# WukongY003.net
KiCad netlist of a schematic drawn in EasyEDA Pro
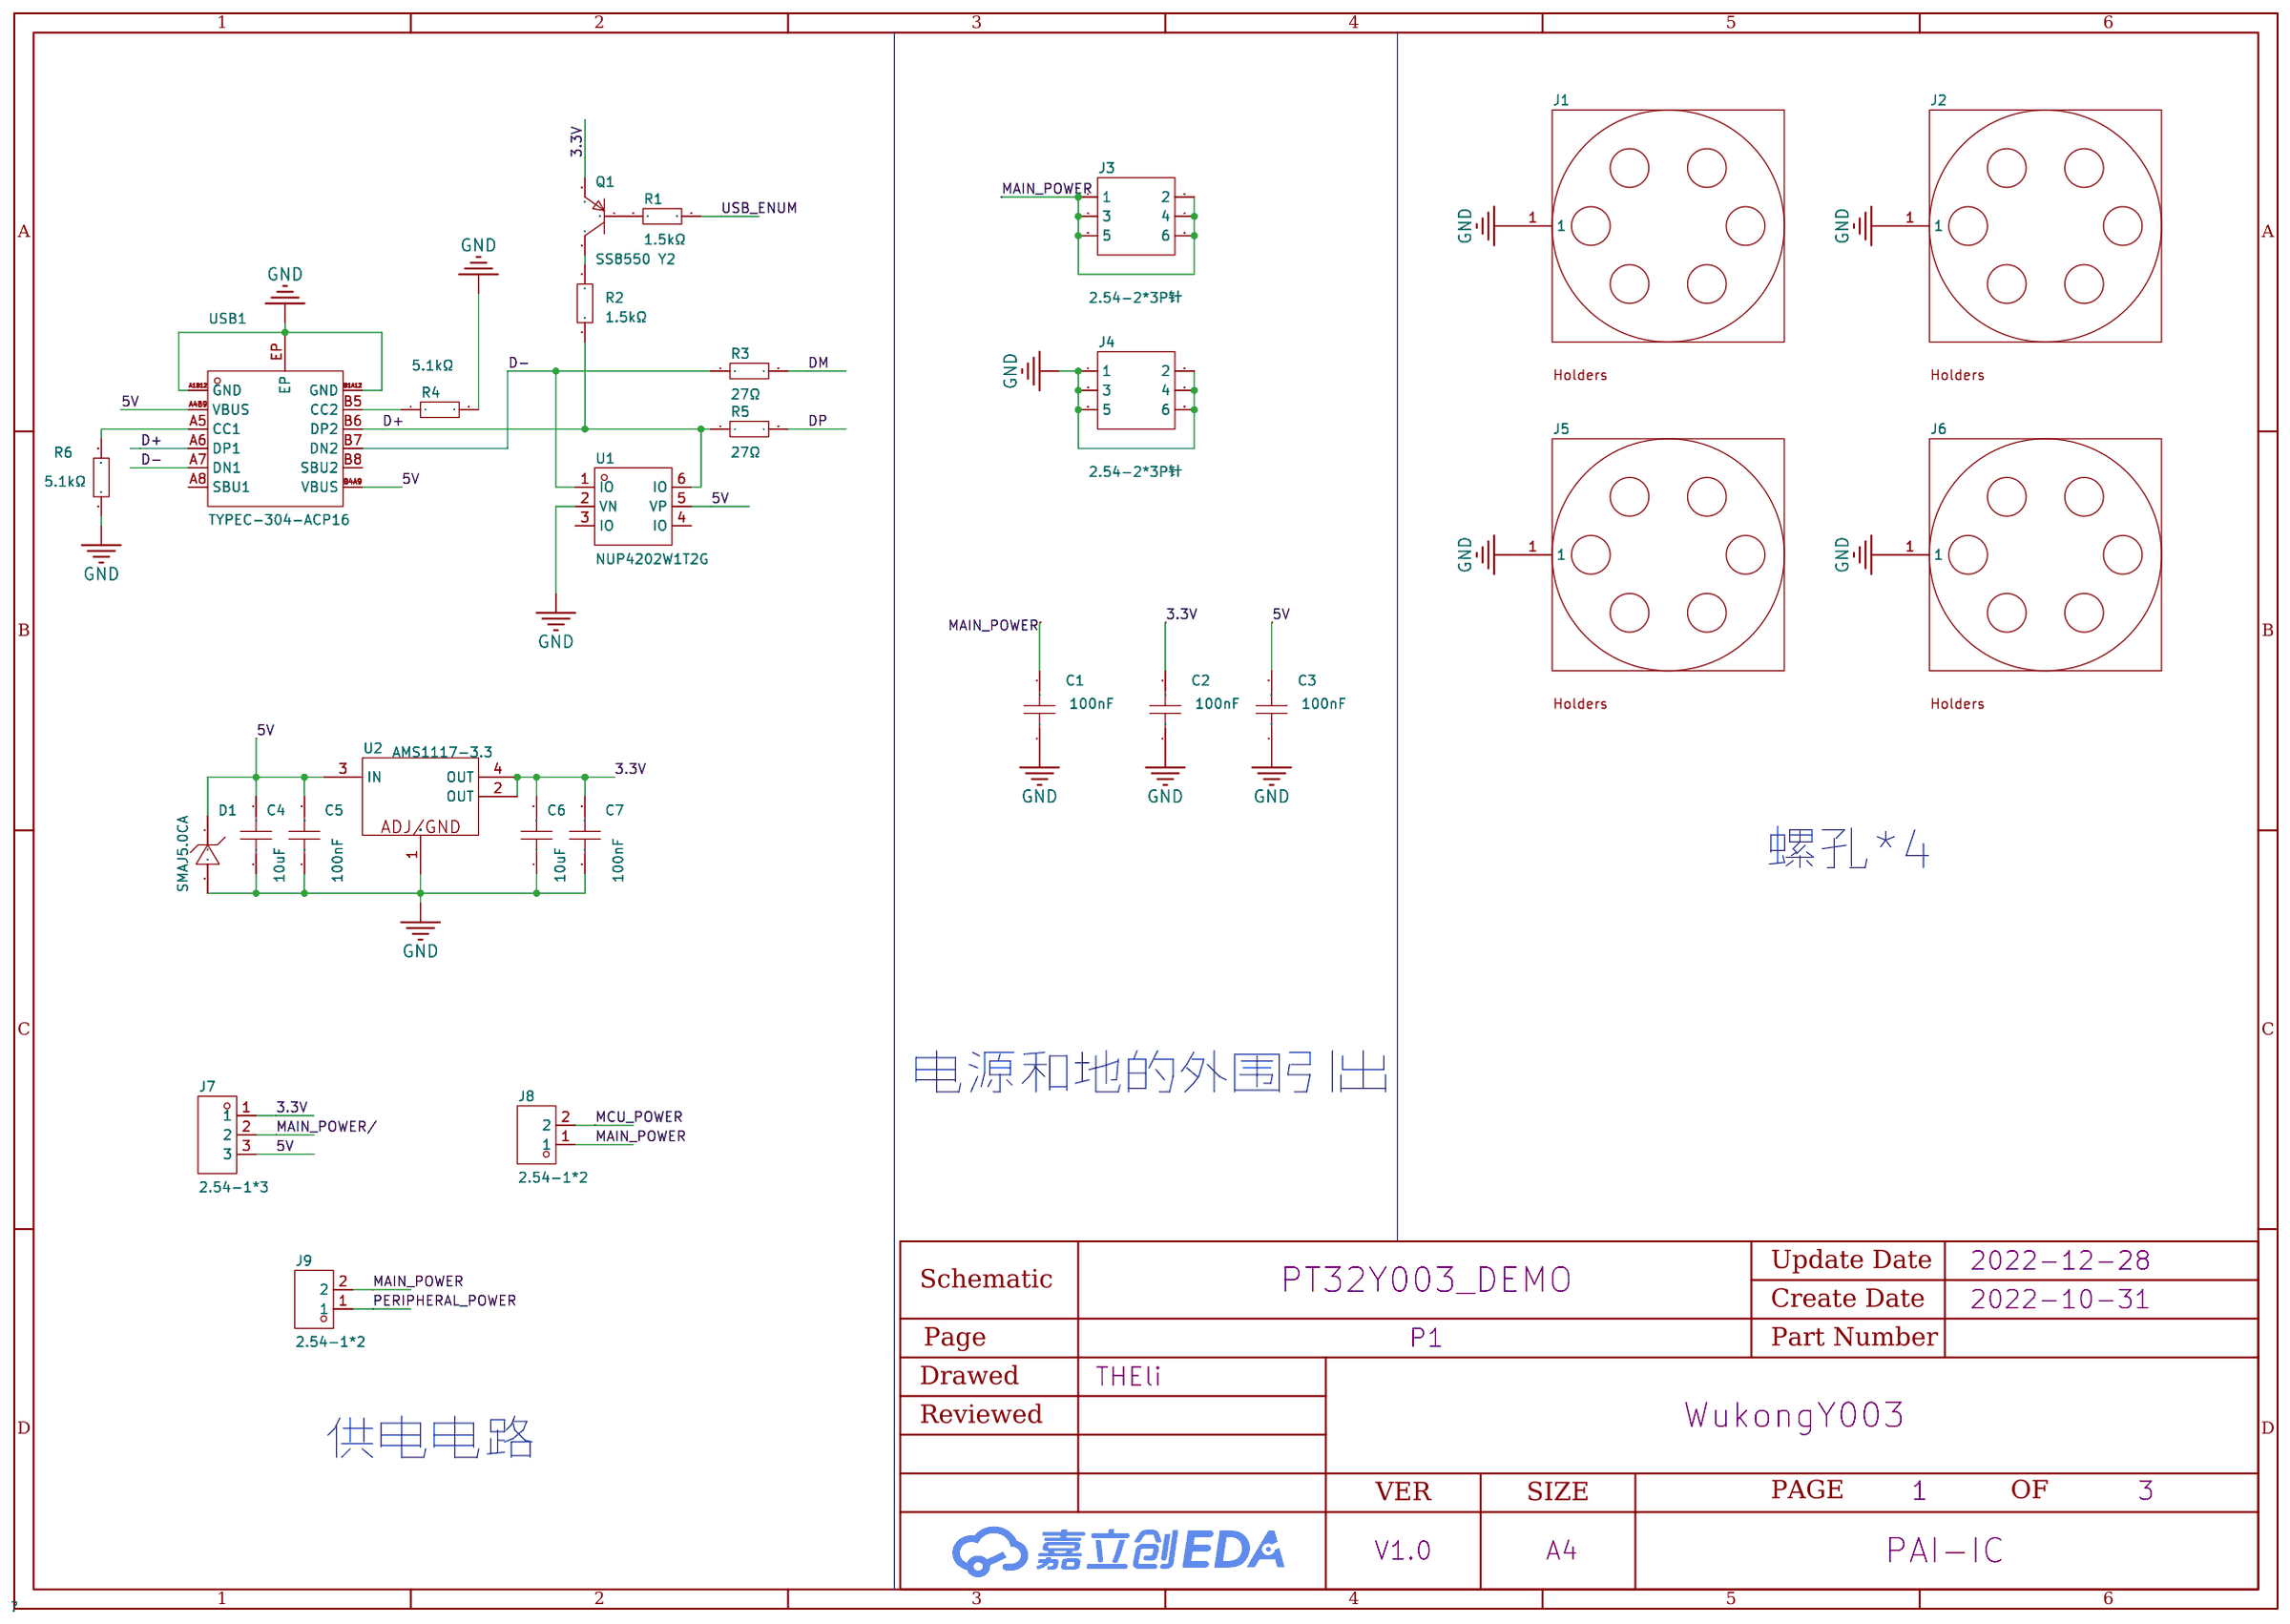
[diagram p0: P1]
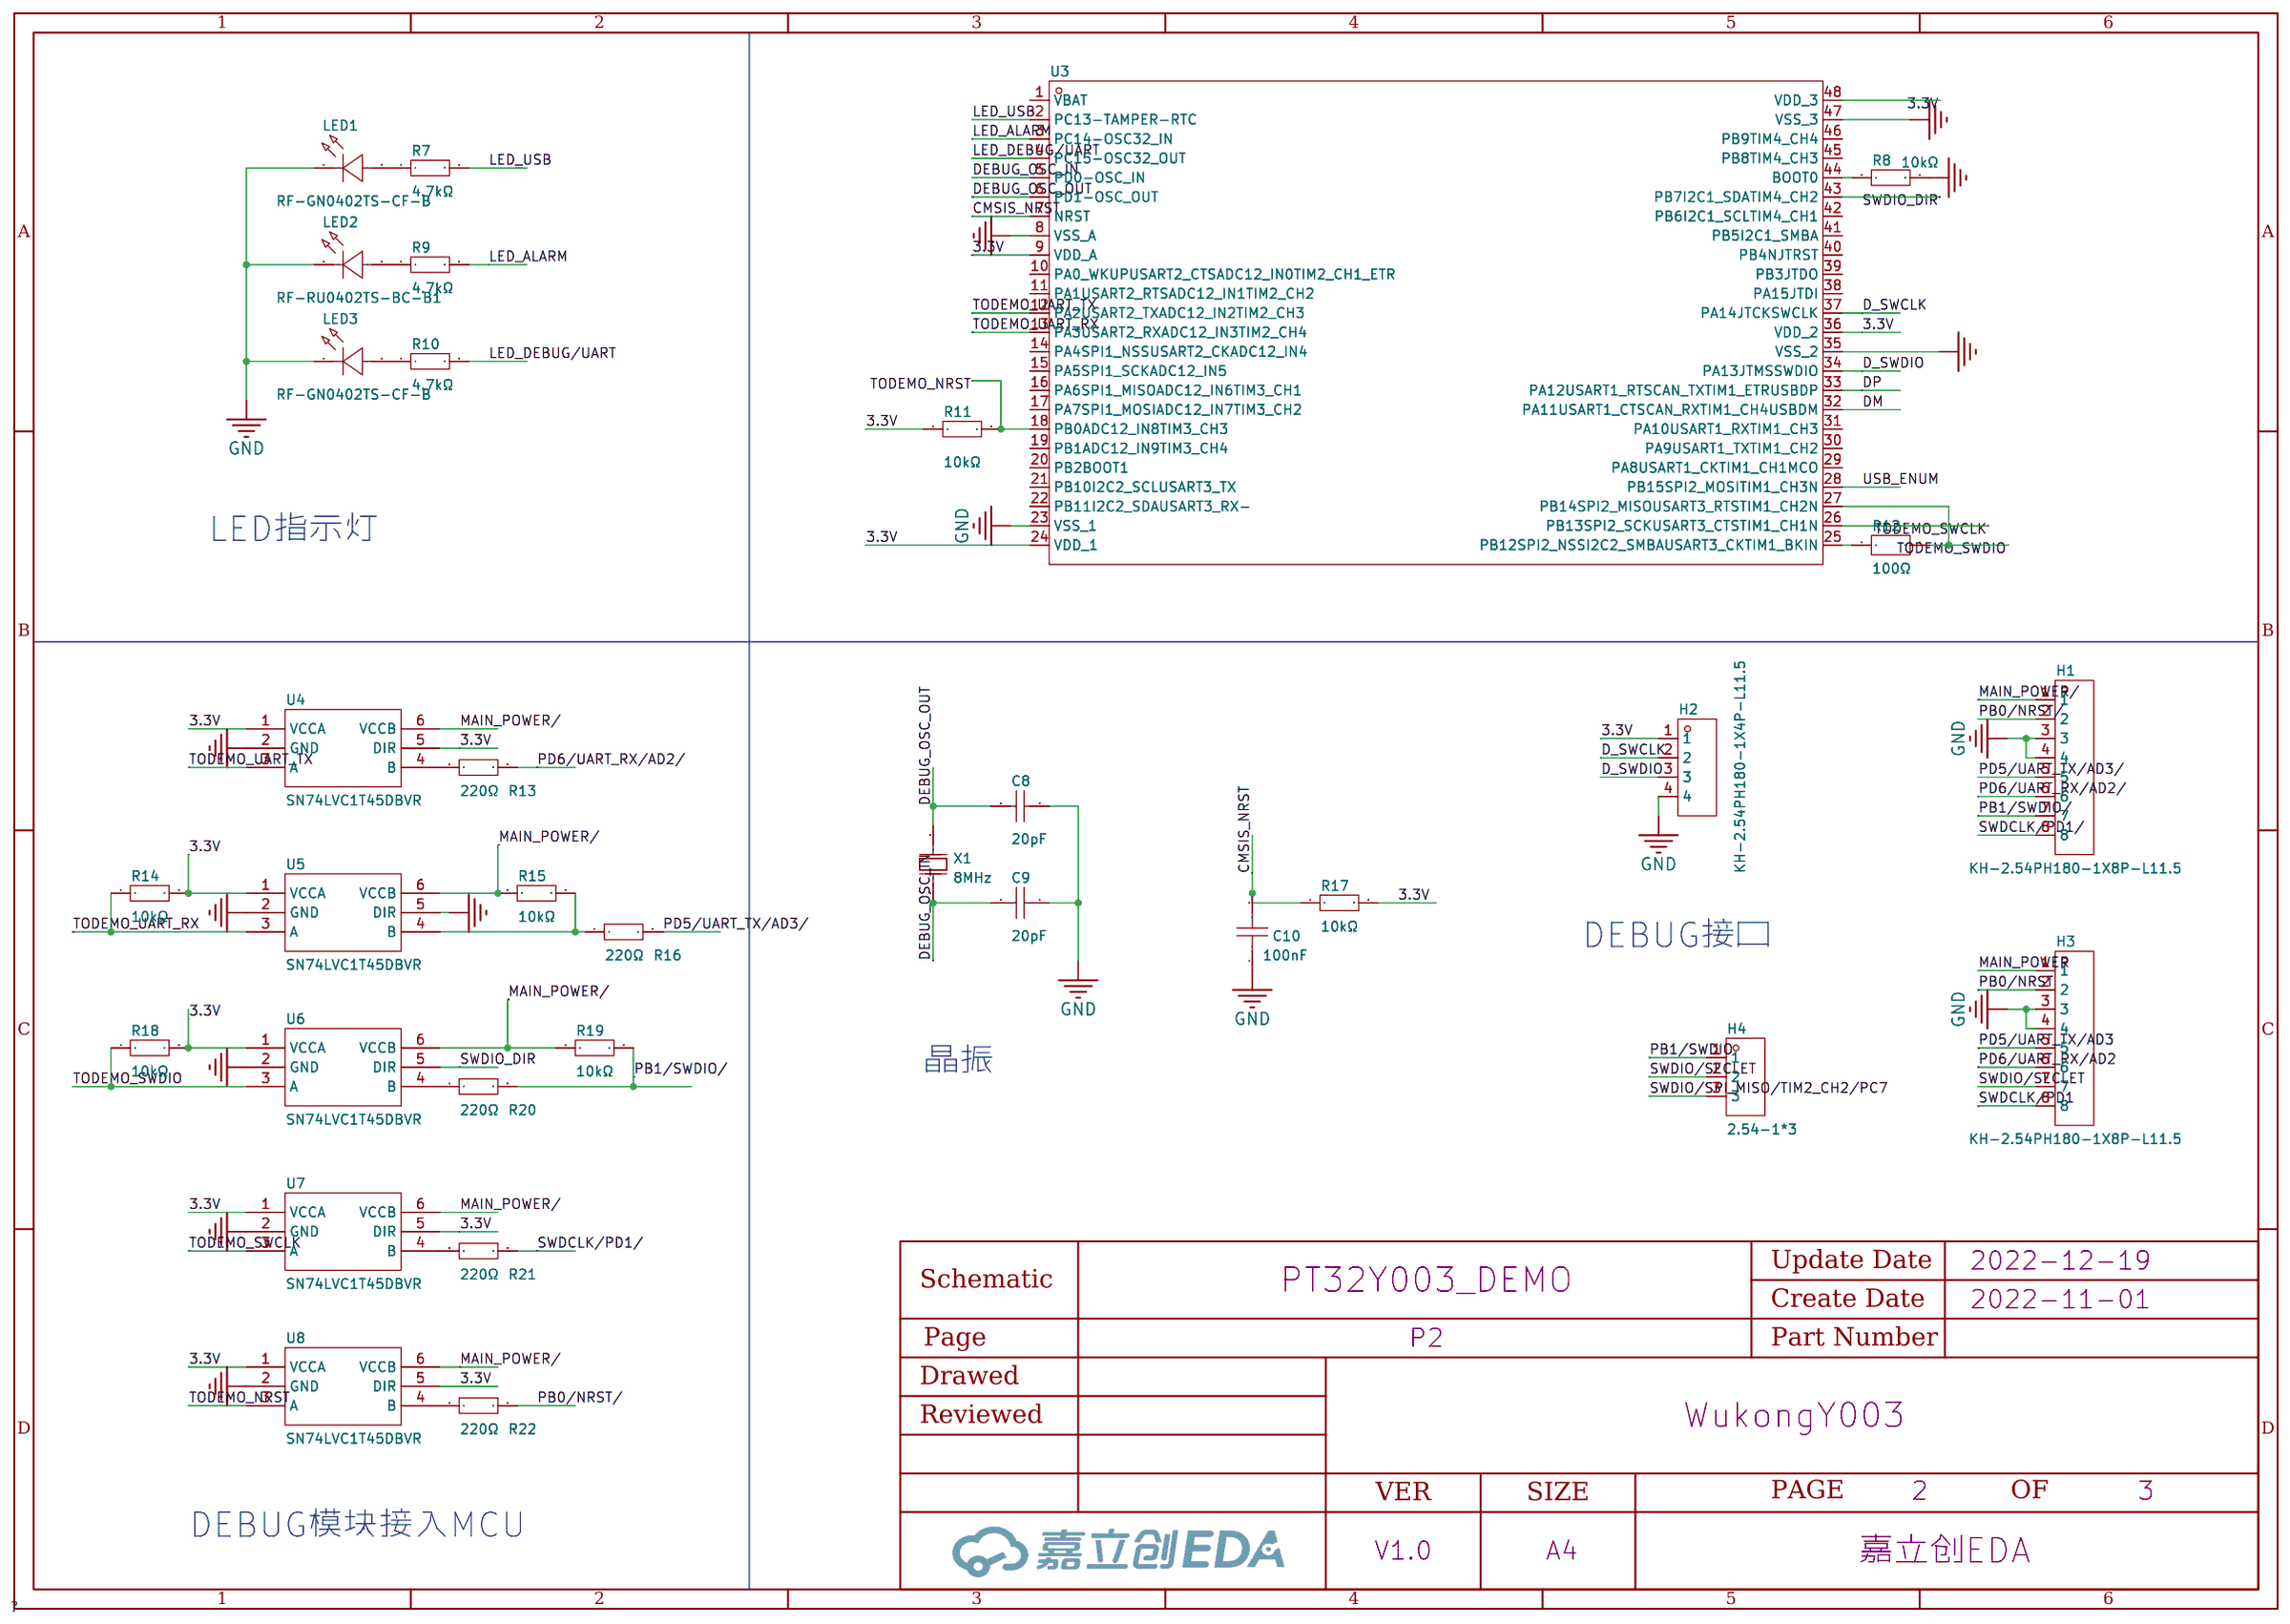
[diagram p1: P2]
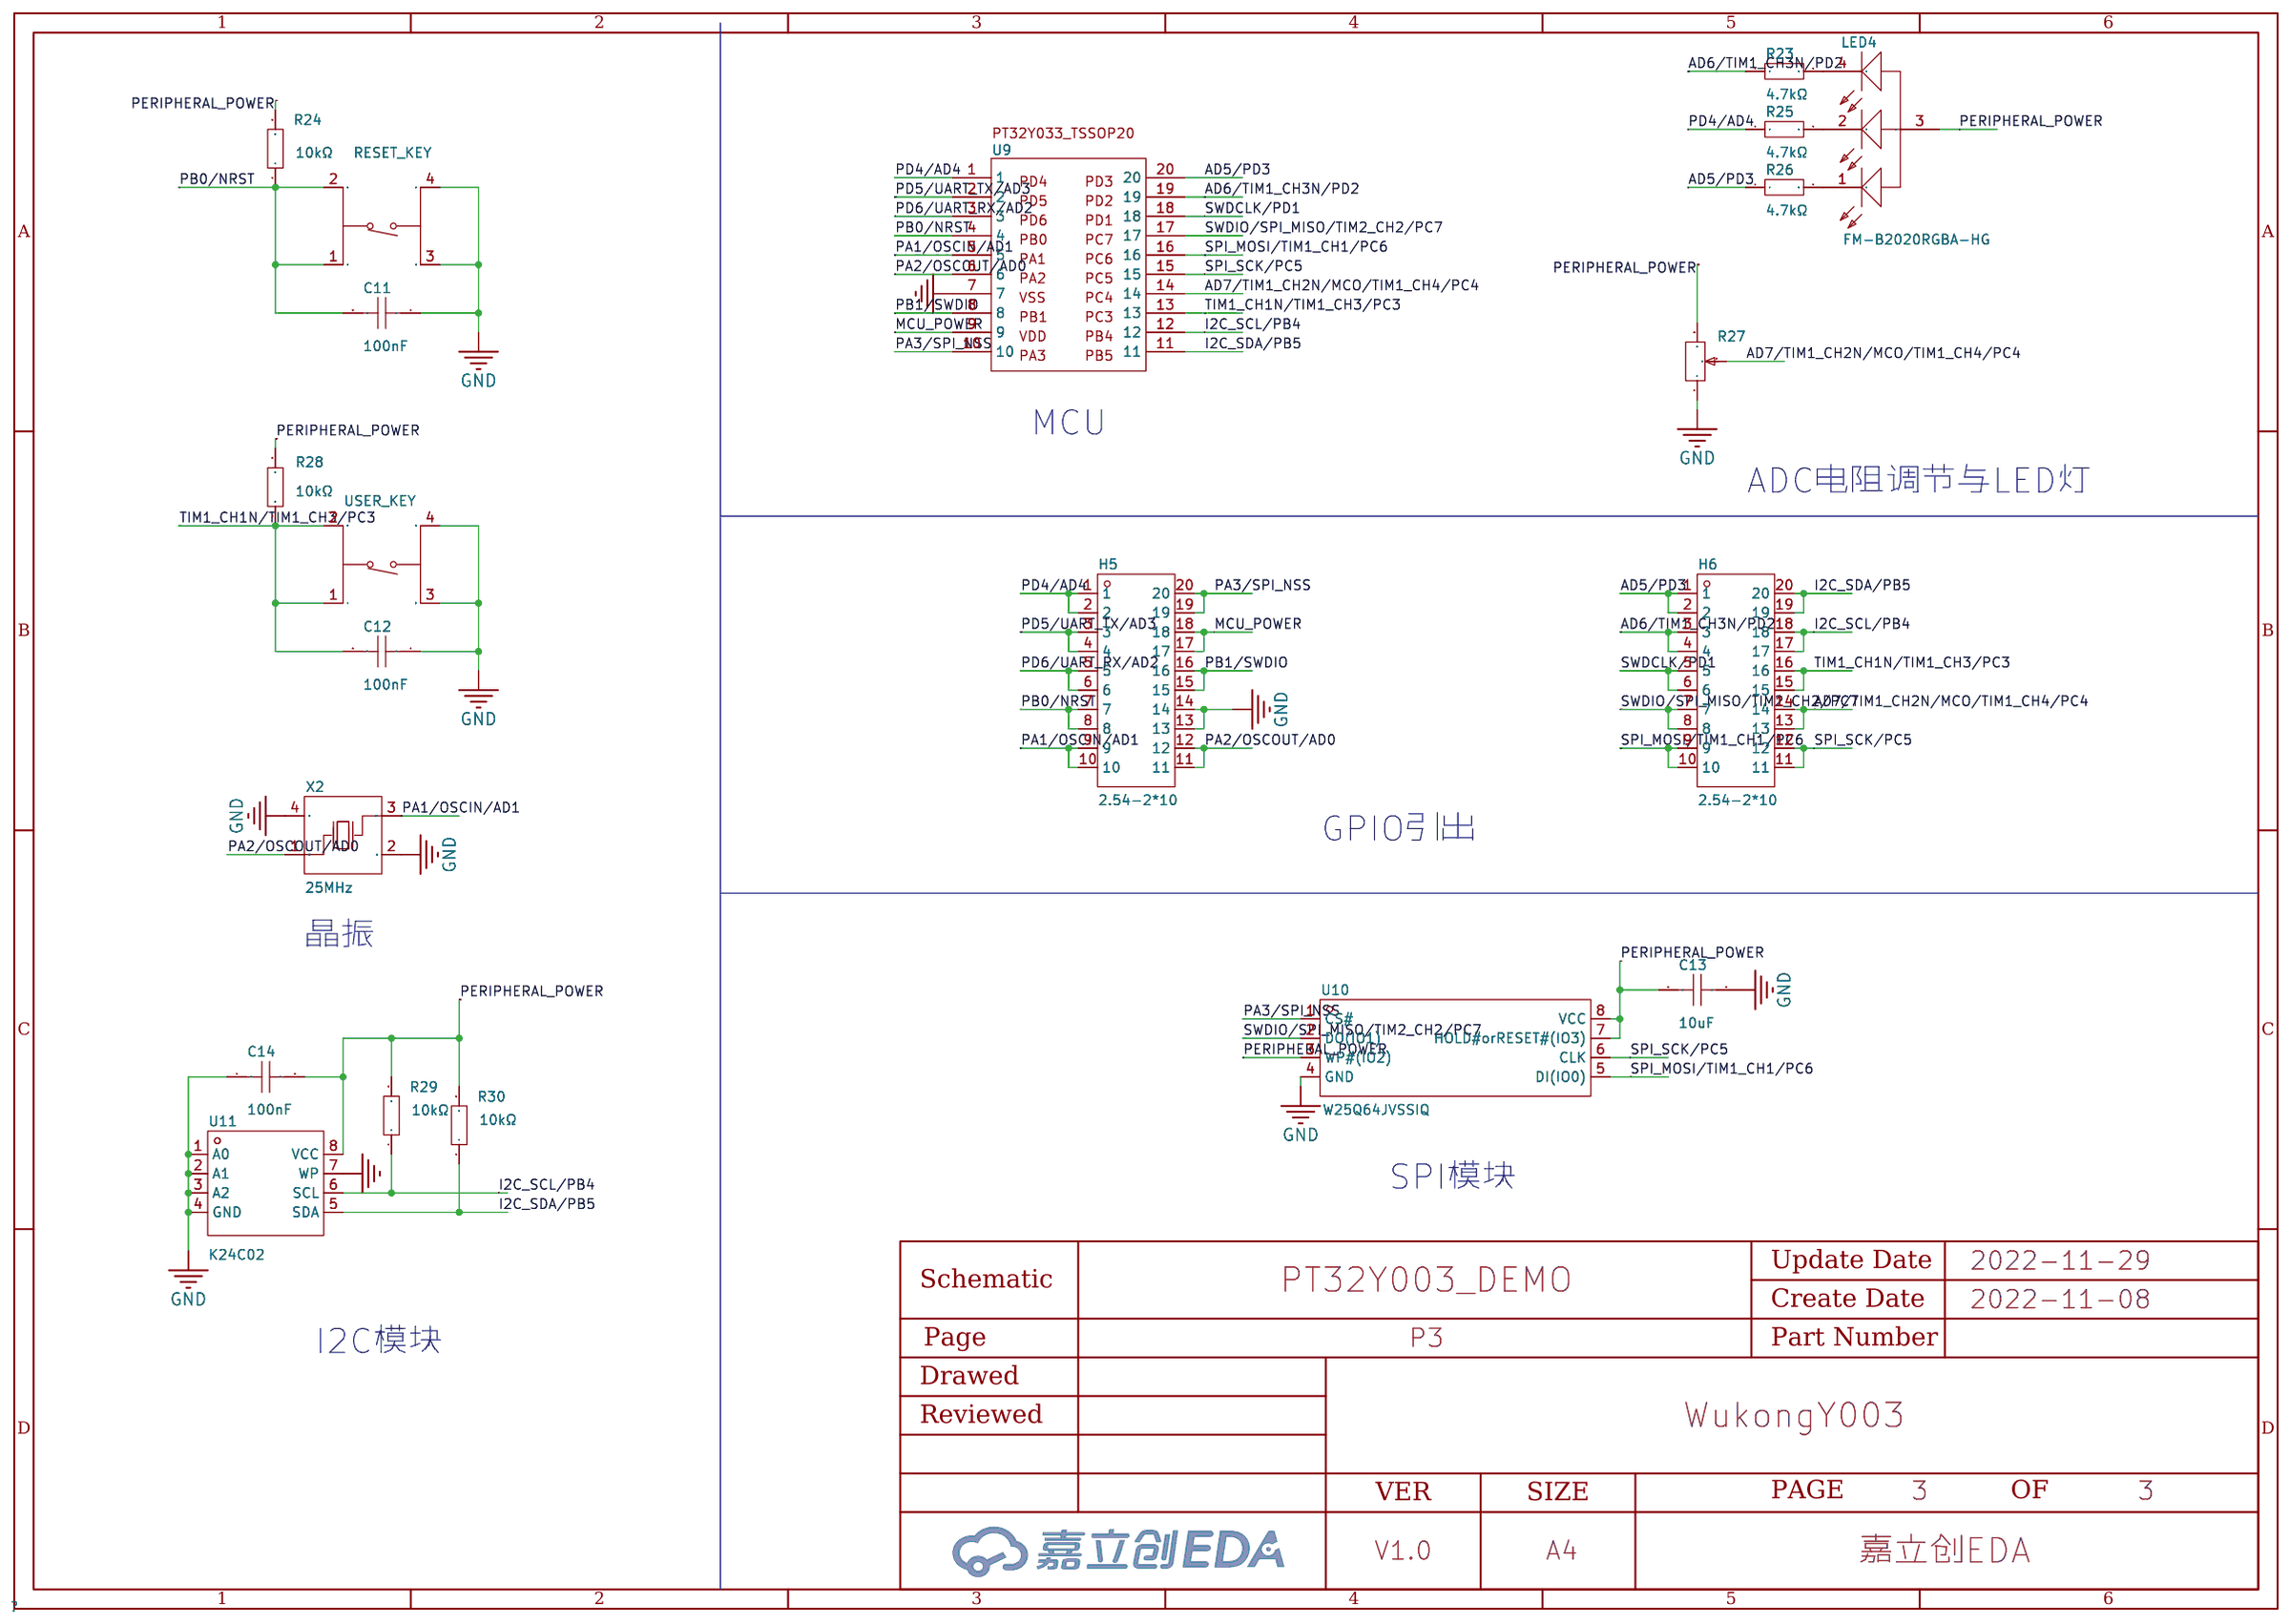
[diagram p2: P3]

(export (version "E")
  (design (tool "Eeschema 10.0.6"))
  (components
    (comp (ref "C1")
      (value "100nF")
      (footprint "easyedapro:C0603")
      (description "容值:100nF;精度:±10%;额定电压:50V;材质(温度系数):X7R;")
      (fields
        (field (name "Manufacturer Part") "CC0603KRX7R9BB104")
        (field (name "Manufacturer") "YAGEO(国巨)")
      )
      (libsource (lib "easyedapro") (part "CC0603KRX7R9BB104"))
    )
    (comp (ref "C2")
      (value "100nF")
      (footprint "easyedapro:C0603")
      (description "容值:100nF;精度:±10%;额定电压:50V;材质(温度系数):X7R;")
      (fields
        (field (name "Manufacturer Part") "CC0603KRX7R9BB104")
        (field (name "Manufacturer") "YAGEO(国巨)")
      )
      (libsource (lib "easyedapro") (part "CC0603KRX7R9BB104"))
    )
    (comp (ref "C3")
      (value "100nF")
      (footprint "easyedapro:C0603")
      (description "容值:100nF;精度:±10%;额定电压:50V;材质(温度系数):X7R;")
      (fields
        (field (name "Manufacturer Part") "CC0603KRX7R9BB104")
        (field (name "Manufacturer") "YAGEO(国巨)")
      )
      (libsource (lib "easyedapro") (part "CC0603KRX7R9BB104"))
    )
    (comp (ref "C4")
      (value "10uF")
      (footprint "easyedapro:C1210")
      (description "容值:10uF;精度:±10%;额定电压:50V;材质(温度系数):X7R;")
      (fields (field (name "Manufacturer Part") "C3225X7R1H106KT000E") (field (name "Manufacturer") "TDK"))
      (libsource (lib "easyedapro") (part "C3225X7R1H106KT000E"))
    )
    (comp (ref "C5")
      (value "100nF")
      (footprint "easyedapro:C0603")
      (description "容值:100nF;精度:±10%;额定电压:50V;材质(温度系数):X7R;")
      (fields
        (field (name "Manufacturer Part") "CC0603KRX7R9BB104")
        (field (name "Manufacturer") "YAGEO(国巨)")
      )
      (libsource (lib "easyedapro") (part "CC0603KRX7R9BB104"))
    )
    (comp (ref "C6")
      (value "10uF")
      (footprint "easyedapro:C1210")
      (description "容值:10uF;精度:±10%;额定电压:50V;材质(温度系数):X7R;")
      (fields (field (name "Manufacturer Part") "C3225X7R1H106KT000E") (field (name "Manufacturer") "TDK"))
      (libsource (lib "easyedapro") (part "C3225X7R1H106KT000E"))
    )
    (comp (ref "C7")
      (value "100nF")
      (footprint "easyedapro:C0603")
      (description "容值:100nF;精度:±10%;额定电压:50V;材质(温度系数):X7R;")
      (fields
        (field (name "Manufacturer Part") "CC0603KRX7R9BB104")
        (field (name "Manufacturer") "YAGEO(国巨)")
      )
      (libsource (lib "easyedapro") (part "CC0603KRX7R9BB104"))
    )
    (comp (ref "D1")
      (value "SMAJ5.0CA")
      (footprint "easyedapro:SMA_L4.3-W2.7-LS4.7-RD")
      (fields (field (name "Manufacturer") "Me-TECH(美台高科)"))
      (libsource (lib "easyedapro") (part "SMAJ5.0CA_C575836"))
    )
    (comp (ref "J1")
      (value "~")
      (footprint "easyedapro:DEMO板安装孔")
      (libsource (lib "easyedapro") (part "螺孔_3.1X6MM"))
    )
    (comp (ref "J2")
      (value "~")
      (footprint "easyedapro:DEMO板安装孔")
      (libsource (lib "easyedapro") (part "螺孔_3.1X6MM"))
    )
    (comp (ref "J3")
      (value "2.54-2*3P针")
      (footprint "easyedapro:HDR-TH_6P-P2.54-V-M-R2-C3-S2.54-1")
      (fields (field (name "Manufacturer") "BOOMELE(博穆精密)"))
      (libsource (lib "easyedapro") (part "Header-Male-2.54_2x3"))
    )
    (comp (ref "J4")
      (value "2.54-2*3P针")
      (footprint "easyedapro:HDR-TH_6P-P2.54-V-M-R2-C3-S2.54-1")
      (fields (field (name "Manufacturer") "BOOMELE(博穆精密)"))
      (libsource (lib "easyedapro") (part "Header-Male-2.54_2x3"))
    )
    (comp (ref "J5")
      (value "~")
      (footprint "easyedapro:DEMO板安装孔")
      (libsource (lib "easyedapro") (part "螺孔_3.1X6MM"))
    )
    (comp (ref "J6")
      (value "~")
      (footprint "easyedapro:DEMO板安装孔")
      (libsource (lib "easyedapro") (part "螺孔_3.1X6MM"))
    )
    (comp (ref "J7")
      (value "2.54-1*3")
      (footprint "easyedapro:HDR-TH_3P-P2.54-V-M-1")
      (description "排针 2.54mm 1x3P 镀金3u")
      (fields (field (name "Manufacturer") "ZHOURI(洲日)"))
      (libsource (lib "easyedapro") (part "2.54-1*3"))
    )
    (comp (ref "J8")
      (value "2.54-1*2")
      (footprint "easyedapro:HDR-TH_2P-P2.54-V-M")
      (description "排针 2.54mm 1x2P 镀金3u")
      (fields (field (name "Manufacturer") "ZHOURI(洲日)"))
      (libsource (lib "easyedapro") (part "2.54-1*2"))
    )
    (comp (ref "J9")
      (value "2.54-1*2")
      (footprint "easyedapro:HDR-TH_2P-P2.54-V-M")
      (description "排针 2.54mm 1x2P 镀金3u")
      (fields (field (name "Manufacturer") "ZHOURI(洲日)"))
      (libsource (lib "easyedapro") (part "2.54-1*2"))
    )
    (comp (ref "Q1")
      (value "SS8550 Y2")
      (footprint "easyedapro:SOT-23-3_L2.9-W1.3-P1.90-LS2.4-BR")
      (fields (field (name "Manufacturer") "CJ(江苏长电/长晶)"))
      (libsource (lib "easyedapro") (part "SS8550_C8542"))
    )
    (comp (ref "R1")
      (value "1.5kΩ")
      (footprint "easyedapro:R0603")
      (description "阻值:1.5kΩ;精度:±1%;温度系数:±100ppm/;功率:1/10W;最大工作电压:75V;工作温度范围:-55~+155;")
      (fields
        (field (name "Manufacturer Part") "0603WAF1501T5E")
        (field (name "Manufacturer") "UNI-ROYAL(厚声)")
      )
      (libsource (lib "easyedapro") (part "0603WAF1501T5E"))
    )
    (comp (ref "R2")
      (value "1.5kΩ")
      (footprint "easyedapro:R0603")
      (description "阻值:1.5kΩ;精度:±1%;温度系数:±100ppm/;功率:1/10W;最大工作电压:75V;工作温度范围:-55~+155;")
      (fields
        (field (name "Manufacturer Part") "0603WAF1501T5E")
        (field (name "Manufacturer") "UNI-ROYAL(厚声)")
      )
      (libsource (lib "easyedapro") (part "0603WAF1501T5E"))
    )
    (comp (ref "R3")
      (value "27Ω")
      (footprint "easyedapro:R0603")
      (description "电阻类型:厚膜电阻;阻值:27Ω;精度:±1%;功率:100mW;温度系数:±200ppm/;最大工作电压:75V;工作温度范围:-55~+155;")
      (fields
        (field (name "Manufacturer Part") "0603WAF270JT5E")
        (field (name "Manufacturer") "UNI-ROYAL(厚声)")
      )
      (libsource (lib "easyedapro") (part "0603WAF270JT5E"))
    )
    (comp (ref "R4")
      (value "5.1kΩ")
      (footprint "easyedapro:R0603")
      (description "阻值:5.1kΩ;精度:±5%;功率:100mW;温度系数:±200ppm/;")
      (fields
        (field (name "Manufacturer Part") "RMC1/16-512JTP")
        (field (name "Manufacturer") "KAMAYA(釜屋電機)")
      )
      (libsource (lib "easyedapro") (part "RMC1/16-512JTP"))
    )
    (comp (ref "R5")
      (value "27Ω")
      (footprint "easyedapro:R0603")
      (description "电阻类型:厚膜电阻;阻值:27Ω;精度:±1%;功率:100mW;温度系数:±200ppm/;最大工作电压:75V;工作温度范围:-55~+155;")
      (fields
        (field (name "Manufacturer Part") "0603WAF270JT5E")
        (field (name "Manufacturer") "UNI-ROYAL(厚声)")
      )
      (libsource (lib "easyedapro") (part "0603WAF270JT5E"))
    )
    (comp (ref "R6")
      (value "5.1kΩ")
      (footprint "easyedapro:R0603")
      (description "阻值:5.1kΩ;精度:±5%;功率:100mW;温度系数:±200ppm/;")
      (fields
        (field (name "Manufacturer Part") "RMC1/16-512JTP")
        (field (name "Manufacturer") "KAMAYA(釜屋電機)")
      )
      (libsource (lib "easyedapro") (part "RMC1/16-512JTP"))
    )
    (comp (ref "U1")
      (value "NUP4202W1T2G")
      (footprint "easyedapro:SOT-363_L2.0-W1.3-P0.65-LS2.1-BR")
      (fields (field (name "Manufacturer") "onsemi(安森美)"))
      (libsource (lib "easyedapro") (part "NUP4202W1T2G"))
    )
    (comp (ref "U2")
      (value "AMS1117-3.3")
      (footprint "easyedapro:SOT-223-3_L6.4-W3.5-P2.30-LS7.0-BR")
      (fields (field (name "Manufacturer") "国芯佳品"))
      (libsource (lib "easyedapro") (part "AMS1117-3.3_C2992570"))
    )
    (comp (ref "USB1")
      (value "TYPEC-304-ACP16")
      (footprint "easyedapro:USB-C-SMD_TYPE-C-16P-1")
      (description "连接器类型:-;标准:-;公母:-;触点数量:-;端口数量:-;安装方式:-;额定电流 - 电源:-;触头材质:-;触头镀层:-;工作温度范围:-;")
      (fields (field (name "Manufacturer") "XUNPU(讯普)"))
      (libsource (lib "easyedapro") (part "TYPEC-304-ACP16"))
    )
    (comp (ref "C8")
      (value "20pF")
      (footprint "easyedapro:C0603")
      (description "容值:20pF;精度:±5%;额定电压:50V;材质(温度系数):C0G;")
      (fields
        (field (name "Manufacturer Part") "GRM1885C1H200JA01D")
        (field (name "Manufacturer") "muRata(村田)")
      )
      (libsource (lib "easyedapro") (part "GRM1885C1H200JA01D"))
    )
    (comp (ref "C9")
      (value "20pF")
      (footprint "easyedapro:C0603")
      (description "容值:20pF;精度:±5%;额定电压:50V;材质(温度系数):C0G;")
      (fields
        (field (name "Manufacturer Part") "GRM1885C1H200JA01D")
        (field (name "Manufacturer") "muRata(村田)")
      )
      (libsource (lib "easyedapro") (part "GRM1885C1H200JA01D"))
    )
    (comp (ref "C10")
      (value "100nF")
      (footprint "easyedapro:C0603")
      (description "容值:100nF;精度:±10%;额定电压:50V;材质(温度系数):X7R;")
      (fields
        (field (name "Manufacturer Part") "TCC0603X7R104K500CT")
        (field (name "Manufacturer") "CCTC(三环)")
      )
      (libsource (lib "easyedapro") (part "TCC0603X7R104K500CT"))
    )
    (comp (ref "H1")
      (value "KH-2.54PH180-1X8P-L11.5")
      (footprint "easyedapro:HDR-TH_8P-P2.54-V-M")
      (fields (field (name "Manufacturer") "kinghelm(金航标)"))
      (libsource (lib "easyedapro") (part "KH-2.54PH180-1X8P-L11.5"))
    )
    (comp (ref "H2")
      (value "KH-2.54PH180-1X4P-L11.5")
      (footprint "easyedapro:HDR-TH_4P-P2.54-V-M")
      (fields (field (name "Manufacturer") "kinghelm(金航标)"))
      (libsource (lib "easyedapro") (part "KH-2.54PH180-1X4P-L11.5"))
    )
    (comp (ref "H3")
      (value "KH-2.54PH180-1X8P-L11.5")
      (footprint "easyedapro:HDR-TH_8P-P2.54-V-M")
      (fields (field (name "Manufacturer") "kinghelm(金航标)"))
      (libsource (lib "easyedapro") (part "KH-2.54PH180-1X8P-L11.5"))
    )
    (comp (ref "H4")
      (value "2.54-1*3")
      (footprint "easyedapro:HDR-TH_3P-P2.54-V-M-1")
      (description "排针 2.54mm 1x3P 镀金3u")
      (fields (field (name "Manufacturer") "ZHOURI(洲日)"))
      (libsource (lib "easyedapro") (part "2.54-1*3"))
    )
    (comp (ref "LED1")
      (value "RF-GN0402TS-CF-B")
      (footprint "easyedapro:LED0402-RD_GREEN")
      (fields (field (name "Manufacturer") "Refond(瑞丰)"))
      (libsource (lib "easyedapro") (part "RF-GN0402TS-CF-B"))
    )
    (comp (ref "LED2")
      (value "RF-RU0402TS-BC-B1")
      (footprint "easyedapro:LED0402-RD_RED")
      (fields (field (name "Manufacturer") "Refond(瑞丰)"))
      (libsource (lib "easyedapro") (part "RF-RU0402TS-BC-B1"))
    )
    (comp (ref "LED3")
      (value "RF-GN0402TS-CF-B")
      (footprint "easyedapro:LED0402-RD_GREEN")
      (fields (field (name "Manufacturer") "Refond(瑞丰)"))
      (libsource (lib "easyedapro") (part "RF-GN0402TS-CF-B"))
    )
    (comp (ref "R7")
      (value "4.7kΩ")
      (footprint "easyedapro:R0603")
      (description "阻值:4.7kΩ;精度:±1%;功率:100mW;温度系数:±100ppm/;最大工作电压:50V;工作温度范围:-55~+155;")
      (fields (field (name "Manufacturer Part") "RS-03K4701FT") (field (name "Manufacturer") "FH(风华)"))
      (libsource (lib "easyedapro") (part "RS-03K4701FT"))
    )
    (comp (ref "R8")
      (value "10kΩ")
      (footprint "easyedapro:R0603")
      (description "电阻类型:厚膜电阻;阻值:10kΩ;精度:±5%;功率:100mW;温度系数:±100ppm/;最大工作电压:75V;工作温度范围:-55~+125;")
      (fields (field (name "Manufacturer Part") "RC0603JR-0710KL") (field (name "Manufacturer") "YAGEO(国巨)"))
      (libsource (lib "easyedapro") (part "RC0603JR-0710KL"))
    )
    (comp (ref "R9")
      (value "4.7kΩ")
      (footprint "easyedapro:R0603")
      (description "阻值:4.7kΩ;精度:±1%;功率:100mW;温度系数:±100ppm/;最大工作电压:50V;工作温度范围:-55~+155;")
      (fields (field (name "Manufacturer Part") "RS-03K4701FT") (field (name "Manufacturer") "FH(风华)"))
      (libsource (lib "easyedapro") (part "RS-03K4701FT"))
    )
    (comp (ref "R10")
      (value "4.7kΩ")
      (footprint "easyedapro:R0603")
      (description "阻值:4.7kΩ;精度:±1%;功率:100mW;温度系数:±100ppm/;最大工作电压:50V;工作温度范围:-55~+155;")
      (fields (field (name "Manufacturer Part") "RS-03K4701FT") (field (name "Manufacturer") "FH(风华)"))
      (libsource (lib "easyedapro") (part "RS-03K4701FT"))
    )
    (comp (ref "R11")
      (value "10kΩ")
      (footprint "easyedapro:R0603")
      (description "电阻类型:厚膜电阻;阻值:10kΩ;精度:±5%;功率:100mW;温度系数:±100ppm/;最大工作电压:75V;工作温度范围:-55~+125;")
      (fields (field (name "Manufacturer Part") "RC0603JR-0710KL") (field (name "Manufacturer") "YAGEO(国巨)"))
      (libsource (lib "easyedapro") (part "RC0603JR-0710KL"))
    )
    (comp (ref "R12")
      (value "100Ω")
      (footprint "easyedapro:R0603")
      (description "电阻类型:厚膜电阻;阻值:100Ω;精度:±5%;功率:100mW;温度系数:±100ppm/;最大工作电压:75V;工作温度范围:-55~+155;")
      (fields (field (name "Manufacturer Part") "0603 ±5% 100Ω") (field (name "Manufacturer") "VO(翔胜)"))
      (libsource (lib "easyedapro") (part "0603 ±5% 100Ω"))
    )
    (comp (ref "R13")
      (value "220Ω")
      (footprint "easyedapro:R0603")
      (fields (field (name "Manufacturer Part") "RC0603FR-07220RL") (field (name "Manufacturer") "YAGEO(国巨)"))
      (libsource (lib "easyedapro") (part "RC0603FR-07220RL"))
    )
    (comp (ref "R14")
      (value "10kΩ")
      (footprint "easyedapro:R0603")
      (description "电阻类型:厚膜电阻;阻值:10kΩ;精度:±5%;功率:100mW;温度系数:±100ppm/;最大工作电压:75V;工作温度范围:-55~+125;")
      (fields (field (name "Manufacturer Part") "RC0603JR-0710KL") (field (name "Manufacturer") "YAGEO(国巨)"))
      (libsource (lib "easyedapro") (part "RC0603JR-0710KL"))
    )
    (comp (ref "R15")
      (value "10kΩ")
      (footprint "easyedapro:R0603")
      (description "电阻类型:厚膜电阻;阻值:10kΩ;精度:±5%;功率:100mW;温度系数:±100ppm/;最大工作电压:75V;工作温度范围:-55~+125;")
      (fields (field (name "Manufacturer Part") "RC0603JR-0710KL") (field (name "Manufacturer") "YAGEO(国巨)"))
      (libsource (lib "easyedapro") (part "RC0603JR-0710KL"))
    )
    (comp (ref "R16")
      (value "220Ω")
      (footprint "easyedapro:R0603")
      (fields (field (name "Manufacturer Part") "RC0603FR-07220RL") (field (name "Manufacturer") "YAGEO(国巨)"))
      (libsource (lib "easyedapro") (part "RC0603FR-07220RL"))
    )
    (comp (ref "R17")
      (value "10kΩ")
      (footprint "easyedapro:R0603")
      (description "电阻类型:厚膜电阻;阻值:10kΩ;精度:±5%;功率:100mW;温度系数:±100ppm/;最大工作电压:75V;工作温度范围:-55~+125;")
      (fields (field (name "Manufacturer Part") "RC0603JR-0710KL") (field (name "Manufacturer") "YAGEO(国巨)"))
      (libsource (lib "easyedapro") (part "RC0603JR-0710KL"))
    )
    (comp (ref "R18")
      (value "10kΩ")
      (footprint "easyedapro:R0603")
      (description "电阻类型:厚膜电阻;阻值:10kΩ;精度:±5%;功率:100mW;温度系数:±100ppm/;最大工作电压:75V;工作温度范围:-55~+125;")
      (fields (field (name "Manufacturer Part") "RC0603JR-0710KL") (field (name "Manufacturer") "YAGEO(国巨)"))
      (libsource (lib "easyedapro") (part "RC0603JR-0710KL"))
    )
    (comp (ref "R19")
      (value "10kΩ")
      (footprint "easyedapro:R0603")
      (description "电阻类型:厚膜电阻;阻值:10kΩ;精度:±5%;功率:100mW;温度系数:±100ppm/;最大工作电压:75V;工作温度范围:-55~+125;")
      (fields (field (name "Manufacturer Part") "RC0603JR-0710KL") (field (name "Manufacturer") "YAGEO(国巨)"))
      (libsource (lib "easyedapro") (part "RC0603JR-0710KL"))
    )
    (comp (ref "R20")
      (value "220Ω")
      (footprint "easyedapro:R0603")
      (fields (field (name "Manufacturer Part") "RC0603FR-07220RL") (field (name "Manufacturer") "YAGEO(国巨)"))
      (libsource (lib "easyedapro") (part "RC0603FR-07220RL"))
    )
    (comp (ref "R21")
      (value "220Ω")
      (footprint "easyedapro:R0603")
      (fields (field (name "Manufacturer Part") "RC0603FR-07220RL") (field (name "Manufacturer") "YAGEO(国巨)"))
      (libsource (lib "easyedapro") (part "RC0603FR-07220RL"))
    )
    (comp (ref "R22")
      (value "220Ω")
      (footprint "easyedapro:R0603")
      (fields (field (name "Manufacturer Part") "RC0603FR-07220RL") (field (name "Manufacturer") "YAGEO(国巨)"))
      (libsource (lib "easyedapro") (part "RC0603FR-07220RL"))
    )
    (comp (ref "U3")
      (value "STM32F103CBT6")
      (footprint "easyedapro:LQFP-48_L7.0-W7.0-P0.50-LS9.0-BL")
      (description "主频（MAX):72MHz;工作电压:2V ~ 3.6V;")
      (fields (field (name "Manufacturer") "ST(意法半导体)"))
      (libsource (lib "easyedapro") (part "STM32F103CBT6"))
    )
    (comp (ref "U4")
      (value "SN74LVC1T45DBVR")
      (footprint "easyedapro:SOT-23-6_L2.9-W1.6-P0.95-LS2.8-BR")
      (description "SN74LVC1T45 具有可配置电压转换和三态输出的单位双电源总线收发器")
      (fields (field (name "Manufacturer") "TI(德州仪器)"))
      (libsource (lib "easyedapro") (part "SN74LVC1T45DBVR"))
    )
    (comp (ref "U5")
      (value "SN74LVC1T45DBVR")
      (footprint "easyedapro:SOT-23-6_L2.9-W1.6-P0.95-LS2.8-BR")
      (description "SN74LVC1T45 具有可配置电压转换和三态输出的单位双电源总线收发器")
      (fields (field (name "Manufacturer") "TI(德州仪器)"))
      (libsource (lib "easyedapro") (part "SN74LVC1T45DBVR"))
    )
    (comp (ref "U6")
      (value "SN74LVC1T45DBVR")
      (footprint "easyedapro:SOT-23-6_L2.9-W1.6-P0.95-LS2.8-BR")
      (description "SN74LVC1T45 具有可配置电压转换和三态输出的单位双电源总线收发器")
      (fields (field (name "Manufacturer") "TI(德州仪器)"))
      (libsource (lib "easyedapro") (part "SN74LVC1T45DBVR"))
    )
    (comp (ref "U7")
      (value "SN74LVC1T45DBVR")
      (footprint "easyedapro:SOT-23-6_L2.9-W1.6-P0.95-LS2.8-BR")
      (description "SN74LVC1T45 具有可配置电压转换和三态输出的单位双电源总线收发器")
      (fields (field (name "Manufacturer") "TI(德州仪器)"))
      (libsource (lib "easyedapro") (part "SN74LVC1T45DBVR"))
    )
    (comp (ref "U8")
      (value "SN74LVC1T45DBVR")
      (footprint "easyedapro:SOT-23-6_L2.9-W1.6-P0.95-LS2.8-BR")
      (description "SN74LVC1T45 具有可配置电压转换和三态输出的单位双电源总线收发器")
      (fields (field (name "Manufacturer") "TI(德州仪器)"))
      (libsource (lib "easyedapro") (part "SN74LVC1T45DBVR"))
    )
    (comp (ref "X1")
      (value "8MHz")
      (footprint "easyedapro:CRYSTAL-SMD_L5.0-W3.2")
      (description "频率:8MHz;频率公差:±30ppm;频率稳定度:±150ppm;负载电容:8pF;等效串联电阻(ESR):100Ω;工作温度:-40~+150;")
      (fields (field (name "Manufacturer Part") "ECS-80-8-30Q-VY-TR") (field (name "Manufacturer") "ECS"))
      (libsource (lib "easyedapro") (part "ECS-80-8-30Q-VY-TR"))
    )
    (comp (ref "C11")
      (value "100nF")
      (footprint "easyedapro:C0603")
      (description "容值:100nF;精度:±10%;额定电压:50V;材质(温度系数):X7R;")
      (fields
        (field (name "Manufacturer Part") "TCC0603X7R104K500CT")
        (field (name "Manufacturer") "CCTC(三环)")
      )
      (libsource (lib "easyedapro") (part "TCC0603X7R104K500CT"))
    )
    (comp (ref "C12")
      (value "100nF")
      (footprint "easyedapro:C0603")
      (description "容值:100nF;精度:±10%;额定电压:50V;材质(温度系数):X7R;")
      (fields
        (field (name "Manufacturer Part") "TCC0603X7R104K500CT")
        (field (name "Manufacturer") "CCTC(三环)")
      )
      (libsource (lib "easyedapro") (part "TCC0603X7R104K500CT"))
    )
    (comp (ref "C13")
      (value "10uF")
      (footprint "easyedapro:C1210")
      (description "容值:10uF;精度:±10%;额定电压:50V;材质(温度系数):X7R;")
      (fields (field (name "Manufacturer Part") "C3225X7R1H106KT000E") (field (name "Manufacturer") "TDK"))
      (libsource (lib "easyedapro") (part "C3225X7R1H106KT000E"))
    )
    (comp (ref "C14")
      (value "100nF")
      (footprint "easyedapro:C0603")
      (description "容值:100nF;精度:±10%;额定电压:50V;材质(温度系数):X7R;")
      (fields
        (field (name "Manufacturer Part") "CC0603KRX7R9BB104")
        (field (name "Manufacturer") "YAGEO(国巨)")
      )
      (libsource (lib "easyedapro") (part "CC0603KRX7R9BB104"))
    )
    (comp (ref "H5")
      (value "2.54-2*10")
      (footprint "easyedapro:HDR-TH_20P-P2.54-V-M-R2-C10-S2.54")
      (description "排针 2*10 2.54 11.6 MMROHS")
      (fields (field (name "Manufacturer") "ZHOURI(洲日)"))
      (libsource (lib "easyedapro") (part "2.54-2*10"))
    )
    (comp (ref "H6")
      (value "2.54-2*10")
      (footprint "easyedapro:HDR-TH_20P-P2.54-V-M-R2-C10-S2.54")
      (description "排针 2*10 2.54 11.6 MMROHS")
      (fields (field (name "Manufacturer") "ZHOURI(洲日)"))
      (libsource (lib "easyedapro") (part "2.54-2*10"))
    )
    (comp (ref "LED4")
      (value "FM-B2020RGBA-HG")
      (footprint "easyedapro:LED-SMD_FM-B2020RGBA-HG")
      (description "发光颜色:RGB三色;")
      (fields (field (name "Manufacturer") "国星光电"))
      (libsource (lib "easyedapro") (part "FM-B2020RGBA-HG"))
    )
    (comp (ref "R23")
      (value "4.7kΩ")
      (footprint "easyedapro:R0603")
      (description "阻值:4.7kΩ;精度:±1%;功率:100mW;温度系数:±100ppm/;最大工作电压:50V;工作温度范围:-55~+155;")
      (fields (field (name "Manufacturer Part") "RS-03K4701FT") (field (name "Manufacturer") "FH(风华)"))
      (libsource (lib "easyedapro") (part "RS-03K4701FT"))
    )
    (comp (ref "R24")
      (value "10kΩ")
      (footprint "easyedapro:R0603")
      (description "电阻类型:厚膜电阻;阻值:10kΩ;精度:±5%;功率:100mW;温度系数:±100ppm/;最大工作电压:75V;工作温度范围:-55~+125;")
      (fields (field (name "Manufacturer Part") "RC0603JR-0710KL") (field (name "Manufacturer") "YAGEO(国巨)"))
      (libsource (lib "easyedapro") (part "RC0603JR-0710KL"))
    )
    (comp (ref "R25")
      (value "4.7kΩ")
      (footprint "easyedapro:R0603")
      (description "阻值:4.7kΩ;精度:±1%;功率:100mW;温度系数:±100ppm/;最大工作电压:50V;工作温度范围:-55~+155;")
      (fields (field (name "Manufacturer Part") "RS-03K4701FT") (field (name "Manufacturer") "FH(风华)"))
      (libsource (lib "easyedapro") (part "RS-03K4701FT"))
    )
    (comp (ref "R26")
      (value "4.7kΩ")
      (footprint "easyedapro:R0603")
      (description "阻值:4.7kΩ;精度:±1%;功率:100mW;温度系数:±100ppm/;最大工作电压:50V;工作温度范围:-55~+155;")
      (fields (field (name "Manufacturer Part") "RS-03K4701FT") (field (name "Manufacturer") "FH(风华)"))
      (libsource (lib "easyedapro") (part "RS-03K4701FT"))
    )
    (comp (ref "R27")
      (value "环保  3362P-1-101LF")
      (footprint "easyedapro:RES-ADJ-TH_3362P")
      (description "精度:±10%;温度系数:±250ppm/;")
      (libsource (lib "easyedapro") (part "RHOS 3362P-1-101LF"))
    )
    (comp (ref "R28")
      (value "10kΩ")
      (footprint "easyedapro:R0603")
      (description "电阻类型:厚膜电阻;阻值:10kΩ;精度:±5%;功率:100mW;温度系数:±100ppm/;最大工作电压:75V;工作温度范围:-55~+125;")
      (fields (field (name "Manufacturer Part") "RC0603JR-0710KL") (field (name "Manufacturer") "YAGEO(国巨)"))
      (libsource (lib "easyedapro") (part "RC0603JR-0710KL"))
    )
    (comp (ref "R29")
      (value "10kΩ")
      (footprint "easyedapro:R0603")
      (description "电阻类型:厚膜电阻;阻值:10kΩ;精度:±5%;功率:100mW;温度系数:±100ppm/;最大工作电压:75V;工作温度范围:-55~+125;")
      (fields (field (name "Manufacturer Part") "RC0603JR-0710KL") (field (name "Manufacturer") "YAGEO(国巨)"))
      (libsource (lib "easyedapro") (part "RC0603JR-0710KL"))
    )
    (comp (ref "R30")
      (value "10kΩ")
      (footprint "easyedapro:R0603")
      (description "电阻类型:厚膜电阻;阻值:10kΩ;精度:±5%;功率:100mW;温度系数:±100ppm/;最大工作电压:75V;工作温度范围:-55~+125;")
      (fields (field (name "Manufacturer Part") "RC0603JR-0710KL") (field (name "Manufacturer") "YAGEO(国巨)"))
      (libsource (lib "easyedapro") (part "RC0603JR-0710KL"))
    )
    (comp (ref "RESET_KEY")
      (value "1TS001G-2500-1500-CT")
      (footprint "easyedapro:SW-SMD_4P-L5.1-W5.1-P3.70-LS6.5-TL-2")
      (description "触点电流:20mA;额定电压(DC):12V;电路结构:单刀单掷;安装方式:立贴;按钮形状:圆形按钮;带灯:-;开关长度:5.1mm;开关宽度:5.1mm;开关高度:0.3mm;")
      (fields (field (name "Manufacturer") "HYP(鸿源精密)"))
      (libsource (lib "easyedapro") (part "1TS001G-2500-1500"))
    )
    (comp (ref "U9") (value "~") (libsource (lib "easyedapro") (part "PT32Y003_TSSOP20")))
    (comp (ref "U10")
      (value "W25Q64JVSSIQ")
      (footprint "easyedapro:SOIC-8_L5.3-W5.3-P1.27-LS8.0-BL")
      (description "存储器类型:-;存储器构架(格式):-;技术:-;存储器容量:-;时钟频率:-;存储器接口类型:-;")
      (fields (field (name "Manufacturer") "WINBOND(华邦)"))
      (libsource (lib "easyedapro") (part "W25Q64JVSSIQ_C179171"))
    )
    (comp (ref "U11")
      (value "K24C02")
      (footprint "easyedapro:SOIC-8_L4.9-W3.9-P1.27-LS6.0-BL")
      (description "2-Kbit(256 x 8bit)，I2C接口，工作电压：1.7V to 5.5V")
      (fields (field (name "Manufacturer") "华虹宏力"))
      (libsource (lib "easyedapro") (part "K24C02_C10510"))
    )
    (comp (ref "USER_KEY")
      (value "1TS001G-2500-1500-CT")
      (footprint "easyedapro:SW-SMD_4P-L5.1-W5.1-P3.70-LS6.5-TL-2")
      (description "触点电流:20mA;额定电压(DC):12V;电路结构:单刀单掷;安装方式:立贴;按钮形状:圆形按钮;带灯:-;开关长度:5.1mm;开关宽度:5.1mm;开关高度:0.3mm;")
      (fields (field (name "Manufacturer") "HYP(鸿源精密)"))
      (libsource (lib "easyedapro") (part "1TS001G-2500-1500"))
    )
    (comp (ref "X2")
      (value "25MHz")
      (footprint "easyedapro:OSC-SMD_4P-L3.2-W2.5-BL")
      (description "晶振类型:贴片无源晶振;频率:25MHz;频率公差:±10ppm;频率稳定度:±30ppm;负载电容:12pF;工作温度:-40~+85;")
      (fields (field (name "Manufacturer Part") "X322525MOB4SI") (field (name "Manufacturer") "YXC(扬兴晶振)"))
      (libsource (lib "easyedapro") (part "X322525MOB4SI"))
    )
  )
  (nets
    (net (code "1") (name "3.3V") (class "Default")
      (node (ref "C2") (pin "2") (pinfunction "2_2") (pintype "input"))
      (node (ref "C6") (pin "2") (pinfunction "2_2") (pintype "input"))
      (node (ref "C7") (pin "2") (pinfunction "2_2") (pintype "input"))
      (node (ref "H2") (pin "1") (pinfunction "1_1") (pintype "input"))
      (node (ref "J7") (pin "1") (pinfunction "1_1") (pintype "input"))
      (node (ref "Q1") (pin "2") (pinfunction "E_2") (pintype "input"))
      (node (ref "R11") (pin "1") (pinfunction "1_1") (pintype "input"))
      (node (ref "R14") (pin "2") (pinfunction "2_2") (pintype "input"))
      (node (ref "R17") (pin "2") (pinfunction "2_2") (pintype "input"))
      (node (ref "R18") (pin "2") (pinfunction "2_2") (pintype "input"))
      (node (ref "U2") (pin "2") (pinfunction "OUT_2") (pintype "input"))
      (node (ref "U2") (pin "4") (pinfunction "OUT_4") (pintype "input"))
      (node (ref "U3") (pin "24") (pinfunction "VDD_1_24") (pintype "input"))
      (node (ref "U3") (pin "36") (pinfunction "VDD_2_36") (pintype "input"))
      (node (ref "U3") (pin "48") (pinfunction "VDD_3_48") (pintype "input"))
      (node (ref "U3") (pin "9") (pinfunction "VDD_A_9") (pintype "input"))
      (node (ref "U4") (pin "1") (pinfunction "VCCA_1") (pintype "input"))
      (node (ref "U4") (pin "5") (pinfunction "DIR_5") (pintype "input"))
      (node (ref "U5") (pin "1") (pinfunction "VCCA_1") (pintype "input"))
      (node (ref "U6") (pin "1") (pinfunction "VCCA_1") (pintype "input"))
      (node (ref "U7") (pin "1") (pinfunction "VCCA_1") (pintype "input"))
      (node (ref "U7") (pin "5") (pinfunction "DIR_5") (pintype "input"))
      (node (ref "U8") (pin "1") (pinfunction "VCCA_1") (pintype "input"))
      (node (ref "U8") (pin "5") (pinfunction "DIR_5") (pintype "input"))
    )
    (net (code "2") (name "5V") (class "Default")
      (node (ref "C3") (pin "2") (pinfunction "2_2") (pintype "input"))
      (node (ref "C4") (pin "2") (pinfunction "2_2") (pintype "input"))
      (node (ref "C5") (pin "2") (pinfunction "2_2") (pintype "input"))
      (node (ref "D1") (pin "1") (pinfunction "C_1") (pintype "input"))
      (node (ref "J7") (pin "3") (pinfunction "3_3") (pintype "input"))
      (node (ref "U1") (pin "5") (pinfunction "VP_5") (pintype "input"))
      (node (ref "U2") (pin "3") (pinfunction "IN_3") (pintype "input"))
      (node (ref "USB1") (pin "A4B9") (pinfunction "VBUS_A4B9") (pintype "input"))
      (node (ref "USB1") (pin "B4A9") (pinfunction "VBUS_B4A9") (pintype "input"))
    )
    (net (code "3") (name "AD5{slash}PD3") (class "Default")
      (node (ref "H6") (pin "1") (pinfunction "1_1") (pintype "input"))
      (node (ref "H6") (pin "2") (pinfunction "2_2") (pintype "input"))
      (node (ref "R26") (pin "1") (pinfunction "1_1") (pintype "input"))
      (node (ref "U9") (pin "20") (pinfunction "20_20") (pintype "input"))
    )
    (net (code "4") (name "AD6{slash}TIM1_CH3N{slash}PD2") (class "Default")
      (node (ref "H6") (pin "3") (pinfunction "3_3") (pintype "input"))
      (node (ref "H6") (pin "4") (pinfunction "4_4") (pintype "input"))
      (node (ref "R23") (pin "1") (pinfunction "1_1") (pintype "input"))
      (node (ref "U9") (pin "19") (pinfunction "19_19") (pintype "input"))
    )
    (net (code "5") (name "AD7{slash}TIM1_CH2N{slash}MCO{slash}TIM1_CH4{slash}PC4") (class "Default")
      (node (ref "H6") (pin "13") (pinfunction "13_13") (pintype "input"))
      (node (ref "H6") (pin "14") (pinfunction "14_14") (pintype "input"))
      (node (ref "R27") (pin "2") (pinfunction "2_2") (pintype "input"))
      (node (ref "U9") (pin "14") (pinfunction "14_14") (pintype "input"))
    )
    (net (code "6") (name "CMSIS_NRST") (class "Default")
      (node (ref "C10") (pin "2") (pinfunction "2_2") (pintype "input"))
      (node (ref "R17") (pin "1") (pinfunction "1_1") (pintype "input"))
      (node (ref "U3") (pin "7") (pinfunction "NRST_7") (pintype "input"))
    )
    (net (code "7") (name "D+") (class "Default")
      (node (ref "R2") (pin "1") (pinfunction "1_1") (pintype "input"))
      (node (ref "R5") (pin "1") (pinfunction "1_1") (pintype "input"))
      (node (ref "U1") (pin "6") (pinfunction "IO_6") (pintype "input"))
      (node (ref "USB1") (pin "A6") (pinfunction "DP1_A6") (pintype "input"))
      (node (ref "USB1") (pin "B6") (pinfunction "DP2_B6") (pintype "input"))
    )
    (net (code "8") (name "D-") (class "Default")
      (node (ref "R3") (pin "1") (pinfunction "1_1") (pintype "input"))
      (node (ref "U1") (pin "1") (pinfunction "IO_1") (pintype "input"))
      (node (ref "USB1") (pin "A7") (pinfunction "DN1_A7") (pintype "input"))
      (node (ref "USB1") (pin "B7") (pinfunction "DN2_B7") (pintype "input"))
    )
    (net (code "9") (name "DEBUG_OSC_IN") (class "Default")
      (node (ref "C9") (pin "2") (pinfunction "2_2") (pintype "input"))
      (node (ref "U3") (pin "5") (pinfunction "PD0-OSC_IN_5") (pintype "input"))
      (node (ref "X1") (pin "1") (pinfunction "In/Out_1") (pintype "input"))
    )
    (net (code "10") (name "DEBUG_OSC_OUT") (class "Default")
      (node (ref "C8") (pin "2") (pinfunction "2_2") (pintype "input"))
      (node (ref "U3") (pin "6") (pinfunction "PD1-OSC_OUT_6") (pintype "input"))
      (node (ref "X1") (pin "2") (pinfunction "Out/In_2") (pintype "input"))
    )
    (net (code "11") (name "DM") (class "Default")
      (node (ref "R3") (pin "2") (pinfunction "2_2") (pintype "input"))
      (node (ref "U3") (pin "32") (pinfunction "PA11USART1_CTSCAN_RXTIM1_CH4USBDM_32") (pintype "input"))
    )
    (net (code "12") (name "DP") (class "Default")
      (node (ref "R5") (pin "2") (pinfunction "2_2") (pintype "input"))
      (node (ref "U3") (pin "33") (pinfunction "PA12USART1_RTSCAN_TXTIM1_ETRUSBDP_33") (pintype "input"))
    )
    (net (code "13") (name "D_SWCLK") (class "Default")
      (node (ref "H2") (pin "2") (pinfunction "2_2") (pintype "input"))
      (node (ref "U3") (pin "37") (pinfunction "PA14JTCKSWCLK_37") (pintype "input"))
    )
    (net (code "14") (name "D_SWDIO") (class "Default")
      (node (ref "H2") (pin "3") (pinfunction "3_3") (pintype "input"))
      (node (ref "U3") (pin "34") (pinfunction "PA13JTMSSWDIO_34") (pintype "input"))
    )
    (net (code "15") (name "GND") (class "Default")
      (node (ref "C1") (pin "1") (pinfunction "1_1") (pintype "input"))
      (node (ref "C10") (pin "1") (pinfunction "1_1") (pintype "input"))
      (node (ref "C11") (pin "1") (pinfunction "1_1") (pintype "input"))
      (node (ref "C12") (pin "1") (pinfunction "1_1") (pintype "input"))
      (node (ref "C13") (pin "2") (pinfunction "2_2") (pintype "input"))
      (node (ref "C14") (pin "1") (pinfunction "1_1") (pintype "input"))
      (node (ref "C2") (pin "1") (pinfunction "1_1") (pintype "input"))
      (node (ref "C3") (pin "1") (pinfunction "1_1") (pintype "input"))
      (node (ref "C4") (pin "1") (pinfunction "1_1") (pintype "input"))
      (node (ref "C5") (pin "1") (pinfunction "1_1") (pintype "input"))
      (node (ref "C6") (pin "1") (pinfunction "1_1") (pintype "input"))
      (node (ref "C7") (pin "1") (pinfunction "1_1") (pintype "input"))
      (node (ref "C8") (pin "1") (pinfunction "1_1") (pintype "input"))
      (node (ref "C9") (pin "1") (pinfunction "1_1") (pintype "input"))
      (node (ref "D1") (pin "2") (pinfunction "A_2") (pintype "input"))
      (node (ref "H1") (pin "3") (pinfunction "3_3") (pintype "input"))
      (node (ref "H1") (pin "4") (pinfunction "4_4") (pintype "input"))
      (node (ref "H2") (pin "4") (pinfunction "4_4") (pintype "input"))
      (node (ref "H3") (pin "3") (pinfunction "3_3") (pintype "input"))
      (node (ref "H3") (pin "4") (pinfunction "4_4") (pintype "input"))
      (node (ref "H5") (pin "13") (pinfunction "13_13") (pintype "input"))
      (node (ref "H5") (pin "14") (pinfunction "14_14") (pintype "input"))
      (node (ref "J1") (pin "1") (pinfunction "1_1") (pintype "input"))
      (node (ref "J2") (pin "1") (pinfunction "1_1") (pintype "input"))
      (node (ref "J4") (pin "1") (pinfunction "1_1") (pintype "input"))
      (node (ref "J4") (pin "2") (pinfunction "2_2") (pintype "input"))
      (node (ref "J4") (pin "3") (pinfunction "3_3") (pintype "input"))
      (node (ref "J4") (pin "4") (pinfunction "4_4") (pintype "input"))
      (node (ref "J4") (pin "5") (pinfunction "5_5") (pintype "input"))
      (node (ref "J4") (pin "6") (pinfunction "6_6") (pintype "input"))
      (node (ref "J5") (pin "1") (pinfunction "1_1") (pintype "input"))
      (node (ref "J6") (pin "1") (pinfunction "1_1") (pintype "input"))
      (node (ref "LED1") (pin "1") (pinfunction "K_1") (pintype "input"))
      (node (ref "LED2") (pin "1") (pinfunction "K_1") (pintype "input"))
      (node (ref "LED3") (pin "1") (pinfunction "K_1") (pintype "input"))
      (node (ref "R27") (pin "1") (pinfunction "1_1") (pintype "input"))
      (node (ref "R4") (pin "2") (pinfunction "2_2") (pintype "input"))
      (node (ref "R6") (pin "1") (pinfunction "1_1") (pintype "input"))
      (node (ref "R8") (pin "2") (pinfunction "2_2") (pintype "input"))
      (node (ref "RESET_KEY") (pin "3") (pinfunction "C_3") (pintype "input"))
      (node (ref "RESET_KEY") (pin "4") (pinfunction "D_4") (pintype "input"))
      (node (ref "U1") (pin "2") (pinfunction "VN_2") (pintype "input"))
      (node (ref "U10") (pin "4") (pinfunction "GND_4") (pintype "input"))
      (node (ref "U11") (pin "1") (pinfunction "A0_1") (pintype "input"))
      (node (ref "U11") (pin "2") (pinfunction "A1_2") (pintype "input"))
      (node (ref "U11") (pin "3") (pinfunction "A2_3") (pintype "input"))
      (node (ref "U11") (pin "4") (pinfunction "GND_4") (pintype "input"))
      (node (ref "U11") (pin "7") (pinfunction "WP_7") (pintype "input"))
      (node (ref "U2") (pin "1") (pinfunction "ADJ/GND_1") (pintype "input"))
      (node (ref "U3") (pin "23") (pinfunction "VSS_1_23") (pintype "input"))
      (node (ref "U3") (pin "35") (pinfunction "VSS_2_35") (pintype "input"))
      (node (ref "U3") (pin "47") (pinfunction "VSS_3_47") (pintype "input"))
      (node (ref "U3") (pin "8") (pinfunction "VSS_A_8") (pintype "input"))
      (node (ref "U4") (pin "2") (pinfunction "GND_2") (pintype "input"))
      (node (ref "U5") (pin "2") (pinfunction "GND_2") (pintype "input"))
      (node (ref "U5") (pin "5") (pinfunction "DIR_5") (pintype "input"))
      (node (ref "U6") (pin "2") (pinfunction "GND_2") (pintype "input"))
      (node (ref "U7") (pin "2") (pinfunction "GND_2") (pintype "input"))
      (node (ref "U8") (pin "2") (pinfunction "GND_2") (pintype "input"))
      (node (ref "U9") (pin "7") (pinfunction "7_7") (pintype "input"))
      (node (ref "USB1") (pin "A1B12") (pinfunction "GND_A1B12") (pintype "input"))
      (node (ref "USB1") (pin "B1A12") (pinfunction "GND_B1A12") (pintype "input"))
      (node (ref "USB1") (pin "EP") (pinfunction "EP_EP") (pintype "input"))
      (node (ref "USER_KEY") (pin "3") (pinfunction "C_3") (pintype "input"))
      (node (ref "USER_KEY") (pin "4") (pinfunction "D_4") (pintype "input"))
      (node (ref "X2") (pin "2") (pinfunction "GND_2") (pintype "input"))
      (node (ref "X2") (pin "4") (pinfunction "GND_4") (pintype "input"))
    )
    (net (code "16") (name "I2C_SCL{slash}PB4") (class "Default")
      (node (ref "H6") (pin "17") (pinfunction "17_17") (pintype "input"))
      (node (ref "H6") (pin "18") (pinfunction "18_18") (pintype "input"))
      (node (ref "R29") (pin "1") (pinfunction "1_1") (pintype "input"))
      (node (ref "U11") (pin "6") (pinfunction "SCL_6") (pintype "input"))
      (node (ref "U9") (pin "12") (pinfunction "12_12") (pintype "input"))
    )
    (net (code "17") (name "I2C_SDA{slash}PB5") (class "Default")
      (node (ref "H6") (pin "19") (pinfunction "19_19") (pintype "input"))
      (node (ref "H6") (pin "20") (pinfunction "20_20") (pintype "input"))
      (node (ref "R30") (pin "1") (pinfunction "1_1") (pintype "input"))
      (node (ref "U11") (pin "5") (pinfunction "SDA_5") (pintype "input"))
      (node (ref "U9") (pin "11") (pinfunction "11_11") (pintype "input"))
    )
    (net (code "18") (name "LED_ALARM") (class "Default")
      (node (ref "R9") (pin "2") (pinfunction "2_2") (pintype "input"))
      (node (ref "U3") (pin "3") (pinfunction "PC14-OSC32_IN_3") (pintype "input"))
    )
    (net (code "19") (name "LED_DEBUG{slash}UART") (class "Default")
      (node (ref "R10") (pin "2") (pinfunction "2_2") (pintype "input"))
      (node (ref "U3") (pin "4") (pinfunction "PC15-OSC32_OUT_4") (pintype "input"))
    )
    (net (code "20") (name "LED_USB") (class "Default")
      (node (ref "R7") (pin "2") (pinfunction "2_2") (pintype "input"))
      (node (ref "U3") (pin "2") (pinfunction "PC13-TAMPER-RTC_2") (pintype "input"))
    )
    (net (code "21") (name "MAIN_POWER") (class "Default")
      (node (ref "C1") (pin "2") (pinfunction "2_2") (pintype "input"))
      (node (ref "H3") (pin "1") (pinfunction "1_1") (pintype "input"))
      (node (ref "J3") (pin "1") (pinfunction "1_1") (pintype "input"))
      (node (ref "J3") (pin "2") (pinfunction "2_2") (pintype "input"))
      (node (ref "J3") (pin "3") (pinfunction "3_3") (pintype "input"))
      (node (ref "J3") (pin "4") (pinfunction "4_4") (pintype "input"))
      (node (ref "J3") (pin "5") (pinfunction "5_5") (pintype "input"))
      (node (ref "J3") (pin "6") (pinfunction "6_6") (pintype "input"))
      (node (ref "J8") (pin "1") (pinfunction "1_1") (pintype "input"))
      (node (ref "J9") (pin "2") (pinfunction "2_2") (pintype "input"))
    )
    (net (code "22") (name "MAIN_POWER{slash}") (class "Default")
      (node (ref "H1") (pin "1") (pinfunction "1_1") (pintype "input"))
      (node (ref "J7") (pin "2") (pinfunction "2_2") (pintype "input"))
      (node (ref "R15") (pin "1") (pinfunction "1_1") (pintype "input"))
      (node (ref "R19") (pin "1") (pinfunction "1_1") (pintype "input"))
      (node (ref "U4") (pin "6") (pinfunction "VCCB_6") (pintype "input"))
      (node (ref "U5") (pin "6") (pinfunction "VCCB_6") (pintype "input"))
      (node (ref "U6") (pin "6") (pinfunction "VCCB_6") (pintype "input"))
      (node (ref "U7") (pin "6") (pinfunction "VCCB_6") (pintype "input"))
      (node (ref "U8") (pin "6") (pinfunction "VCCB_6") (pintype "input"))
    )
    (net (code "23") (name "MCU_POWER") (class "Default")
      (node (ref "H5") (pin "17") (pinfunction "17_17") (pintype "input"))
      (node (ref "H5") (pin "18") (pinfunction "18_18") (pintype "input"))
      (node (ref "J8") (pin "2") (pinfunction "2_2") (pintype "input"))
      (node (ref "U9") (pin "9") (pinfunction "9_9") (pintype "input"))
    )
    (net (code "24") (name "Net-(LED1-A)") (class "Default")
      (node (ref "LED1") (pin "2") (pinfunction "A_2") (pintype "input"))
      (node (ref "R7") (pin "1") (pinfunction "1_1") (pintype "input"))
    )
    (net (code "25") (name "Net-(LED2-A)") (class "Default")
      (node (ref "LED2") (pin "2") (pinfunction "A_2") (pintype "input"))
      (node (ref "R9") (pin "1") (pinfunction "1_1") (pintype "input"))
    )
    (net (code "26") (name "Net-(LED3-A)") (class "Default")
      (node (ref "LED3") (pin "2") (pinfunction "A_2") (pintype "input"))
      (node (ref "R10") (pin "1") (pinfunction "1_1") (pintype "input"))
    )
    (net (code "27") (name "Net-(LED4-K-Pad1)") (class "Default")
      (node (ref "LED4") (pin "1") (pinfunction "K_1") (pintype "input"))
      (node (ref "R26") (pin "2") (pinfunction "2_2") (pintype "input"))
    )
    (net (code "28") (name "Net-(LED4-K-Pad2)") (class "Default")
      (node (ref "LED4") (pin "2") (pinfunction "K_2") (pintype "input"))
      (node (ref "R25") (pin "2") (pinfunction "2_2") (pintype "input"))
    )
    (net (code "29") (name "Net-(LED4-K-Pad4)") (class "Default")
      (node (ref "LED4") (pin "4") (pinfunction "K_4") (pintype "input"))
      (node (ref "R23") (pin "2") (pinfunction "2_2") (pintype "input"))
    )
    (net (code "30") (name "Net-(Q1-B)") (class "Default")
      (node (ref "Q1") (pin "1") (pinfunction "B_1") (pintype "input"))
      (node (ref "R1") (pin "1") (pinfunction "1_1") (pintype "input"))
    )
    (net (code "31") (name "Net-(Q1-C)") (class "Default")
      (node (ref "Q1") (pin "3") (pinfunction "C_3") (pintype "input"))
      (node (ref "R2") (pin "2") (pinfunction "2_2") (pintype "input"))
    )
    (net (code "32") (name "Net-(U3-BOOT0)") (class "Default")
      (node (ref "R8") (pin "1") (pinfunction "1_1") (pintype "input"))
      (node (ref "U3") (pin "44") (pinfunction "BOOT0_44") (pintype "input"))
    )
    (net (code "33") (name "Net-(U3-PB12SPI2_NSSI2C2_SMBAUSART3_CKTIM1_BKIN)") (class "Default")
      (node (ref "R12") (pin "1") (pinfunction "1_1") (pintype "input"))
      (node (ref "U3") (pin "25") (pinfunction "PB12SPI2_NSSI2C2_SMBAUSART3_CKTIM1_BKIN_25") (pintype "input"))
    )
    (net (code "34") (name "Net-(U4-B)") (class "Default")
      (node (ref "R13") (pin "1") (pinfunction "1_1") (pintype "input"))
      (node (ref "U4") (pin "4") (pinfunction "B_4") (pintype "input"))
    )
    (net (code "35") (name "Net-(U5-B)") (class "Default")
      (node (ref "R15") (pin "2") (pinfunction "2_2") (pintype "input"))
      (node (ref "R16") (pin "1") (pinfunction "1_1") (pintype "input"))
      (node (ref "U5") (pin "4") (pinfunction "B_4") (pintype "input"))
    )
    (net (code "36") (name "Net-(U6-B)") (class "Default")
      (node (ref "R20") (pin "1") (pinfunction "1_1") (pintype "input"))
      (node (ref "U6") (pin "4") (pinfunction "B_4") (pintype "input"))
    )
    (net (code "37") (name "Net-(U7-B)") (class "Default")
      (node (ref "R21") (pin "1") (pinfunction "1_1") (pintype "input"))
      (node (ref "U7") (pin "4") (pinfunction "B_4") (pintype "input"))
    )
    (net (code "38") (name "Net-(U8-B)") (class "Default")
      (node (ref "R22") (pin "1") (pinfunction "1_1") (pintype "input"))
      (node (ref "U8") (pin "4") (pinfunction "B_4") (pintype "input"))
    )
    (net (code "39") (name "Net-(USB1-CC1)") (class "Default")
      (node (ref "R6") (pin "2") (pinfunction "2_2") (pintype "input"))
      (node (ref "USB1") (pin "A5") (pinfunction "CC1_A5") (pintype "input"))
    )
    (net (code "40") (name "Net-(USB1-CC2)") (class "Default")
      (node (ref "R4") (pin "1") (pinfunction "1_1") (pintype "input"))
      (node (ref "USB1") (pin "B5") (pinfunction "CC2_B5") (pintype "input"))
    )
    (net (code "41") (name "PA1{slash}OSCIN{slash}AD1") (class "Default")
      (node (ref "H5") (pin "10") (pinfunction "10_10") (pintype "input"))
      (node (ref "H5") (pin "9") (pinfunction "9_9") (pintype "input"))
      (node (ref "U9") (pin "5") (pinfunction "5_5") (pintype "input"))
      (node (ref "X2") (pin "3") (pinfunction "OSC2_3") (pintype "input"))
    )
    (net (code "42") (name "PA2{slash}OSCOUT{slash}AD0") (class "Default")
      (node (ref "H5") (pin "11") (pinfunction "11_11") (pintype "input"))
      (node (ref "H5") (pin "12") (pinfunction "12_12") (pintype "input"))
      (node (ref "U9") (pin "6") (pinfunction "6_6") (pintype "input"))
      (node (ref "X2") (pin "1") (pinfunction "OSC1_1") (pintype "input"))
    )
    (net (code "43") (name "PA3{slash}SPI_NSS") (class "Default")
      (node (ref "H5") (pin "19") (pinfunction "19_19") (pintype "input"))
      (node (ref "H5") (pin "20") (pinfunction "20_20") (pintype "input"))
      (node (ref "U10") (pin "1") (pinfunction "CS#_1") (pintype "input"))
      (node (ref "U9") (pin "10") (pinfunction "10_10") (pintype "input"))
    )
    (net (code "44") (name "PB0{slash}NRST") (class "Default")
      (node (ref "C11") (pin "2") (pinfunction "2_2") (pintype "input"))
      (node (ref "H3") (pin "2") (pinfunction "2_2") (pintype "input"))
      (node (ref "H5") (pin "7") (pinfunction "7_7") (pintype "input"))
      (node (ref "H5") (pin "8") (pinfunction "8_8") (pintype "input"))
      (node (ref "R24") (pin "1") (pinfunction "1_1") (pintype "input"))
      (node (ref "RESET_KEY") (pin "1") (pinfunction "A_1") (pintype "input"))
      (node (ref "RESET_KEY") (pin "2") (pinfunction "B_2") (pintype "input"))
      (node (ref "U9") (pin "4") (pinfunction "4_4") (pintype "input"))
    )
    (net (code "45") (name "PB0{slash}NRST{slash}") (class "Default")
      (node (ref "H1") (pin "2") (pinfunction "2_2") (pintype "input"))
      (node (ref "R22") (pin "2") (pinfunction "2_2") (pintype "input"))
    )
    (net (code "46") (name "PB1{slash}SWDIO") (class "Default")
      (node (ref "H4") (pin "1") (pinfunction "1_1") (pintype "input"))
      (node (ref "H5") (pin "15") (pinfunction "15_15") (pintype "input"))
      (node (ref "H5") (pin "16") (pinfunction "16_16") (pintype "input"))
      (node (ref "U9") (pin "8") (pinfunction "8_8") (pintype "input"))
    )
    (net (code "47") (name "PB1{slash}SWDIO{slash}") (class "Default")
      (node (ref "H1") (pin "7") (pinfunction "7_7") (pintype "input"))
      (node (ref "R19") (pin "2") (pinfunction "2_2") (pintype "input"))
      (node (ref "R20") (pin "2") (pinfunction "2_2") (pintype "input"))
    )
    (net (code "48") (name "PD4{slash}AD4") (class "Default")
      (node (ref "H5") (pin "1") (pinfunction "1_1") (pintype "input"))
      (node (ref "H5") (pin "2") (pinfunction "2_2") (pintype "input"))
      (node (ref "R25") (pin "1") (pinfunction "1_1") (pintype "input"))
      (node (ref "U9") (pin "1") (pinfunction "1_1") (pintype "input"))
    )
    (net (code "49") (name "PD5{slash}UART_TX{slash}AD3") (class "Default")
      (node (ref "H3") (pin "5") (pinfunction "5_5") (pintype "input"))
      (node (ref "H5") (pin "3") (pinfunction "3_3") (pintype "input"))
      (node (ref "H5") (pin "4") (pinfunction "4_4") (pintype "input"))
      (node (ref "U9") (pin "2") (pinfunction "2_2") (pintype "input"))
    )
    (net (code "50") (name "PD5{slash}UART_TX{slash}AD3{slash}") (class "Default")
      (node (ref "H1") (pin "5") (pinfunction "5_5") (pintype "input"))
      (node (ref "R16") (pin "2") (pinfunction "2_2") (pintype "input"))
    )
    (net (code "51") (name "PD6{slash}UART_RX{slash}AD2") (class "Default")
      (node (ref "H3") (pin "6") (pinfunction "6_6") (pintype "input"))
      (node (ref "H5") (pin "5") (pinfunction "5_5") (pintype "input"))
      (node (ref "H5") (pin "6") (pinfunction "6_6") (pintype "input"))
      (node (ref "U9") (pin "3") (pinfunction "3_3") (pintype "input"))
    )
    (net (code "52") (name "PD6{slash}UART_RX{slash}AD2{slash}") (class "Default")
      (node (ref "H1") (pin "6") (pinfunction "6_6") (pintype "input"))
      (node (ref "R13") (pin "2") (pinfunction "2_2") (pintype "input"))
    )
    (net (code "53") (name "PERIPHERAL_POWER") (class "Default")
      (node (ref "C13") (pin "1") (pinfunction "1_1") (pintype "input"))
      (node (ref "C14") (pin "2") (pinfunction "2_2") (pintype "input"))
      (node (ref "J9") (pin "1") (pinfunction "1_1") (pintype "input"))
      (node (ref "LED4") (pin "3") (pinfunction "A_3") (pintype "input"))
      (node (ref "R24") (pin "2") (pinfunction "2_2") (pintype "input"))
      (node (ref "R27") (pin "3") (pinfunction "3_3") (pintype "input"))
      (node (ref "R28") (pin "2") (pinfunction "2_2") (pintype "input"))
      (node (ref "R29") (pin "2") (pinfunction "2_2") (pintype "input"))
      (node (ref "R30") (pin "2") (pinfunction "2_2") (pintype "input"))
      (node (ref "U10") (pin "3") (pinfunction "WP#(IO2)_3") (pintype "input"))
      (node (ref "U10") (pin "7") (pinfunction "HOLD#orRESET#(IO3)_7") (pintype "input"))
      (node (ref "U10") (pin "8") (pinfunction "VCC_8") (pintype "input"))
      (node (ref "U11") (pin "8") (pinfunction "VCC_8") (pintype "input"))
    )
    (net (code "54") (name "SPI_MOSI{slash}TIM1_CH1{slash}PC6") (class "Default")
      (node (ref "H6") (pin "10") (pinfunction "10_10") (pintype "input"))
      (node (ref "H6") (pin "9") (pinfunction "9_9") (pintype "input"))
      (node (ref "U10") (pin "5") (pinfunction "DI(IO0)_5") (pintype "input"))
      (node (ref "U9") (pin "16") (pinfunction "16_16") (pintype "input"))
    )
    (net (code "55") (name "SPI_SCK{slash}PC5") (class "Default")
      (node (ref "H6") (pin "11") (pinfunction "11_11") (pintype "input"))
      (node (ref "H6") (pin "12") (pinfunction "12_12") (pintype "input"))
      (node (ref "U10") (pin "6") (pinfunction "CLK_6") (pintype "input"))
      (node (ref "U9") (pin "15") (pinfunction "15_15") (pintype "input"))
    )
    (net (code "56") (name "SWDCLK{slash}PD1") (class "Default")
      (node (ref "H3") (pin "8") (pinfunction "8_8") (pintype "input"))
      (node (ref "H6") (pin "5") (pinfunction "5_5") (pintype "input"))
      (node (ref "H6") (pin "6") (pinfunction "6_6") (pintype "input"))
      (node (ref "U9") (pin "18") (pinfunction "18_18") (pintype "input"))
    )
    (net (code "57") (name "SWDCLK{slash}PD1{slash}") (class "Default")
      (node (ref "H1") (pin "8") (pinfunction "8_8") (pintype "input"))
      (node (ref "R21") (pin "2") (pinfunction "2_2") (pintype "input"))
    )
    (net (code "58") (name "SWDIO_DIR") (class "Default")
      (node (ref "U3") (pin "43") (pinfunction "PB7I2C1_SDATIM4_CH2_43") (pintype "input"))
      (node (ref "U6") (pin "5") (pinfunction "DIR_5") (pintype "input"))
    )
    (net (code "59") (name "SWDIO{slash}SECLET") (class "Default")
      (node (ref "H3") (pin "7") (pinfunction "7_7") (pintype "input"))
      (node (ref "H4") (pin "2") (pinfunction "2_2") (pintype "input"))
    )
    (net (code "60") (name "SWDIO{slash}SPI_MISO{slash}TIM2_CH2{slash}PC7") (class "Default")
      (node (ref "H4") (pin "3") (pinfunction "3_3") (pintype "input"))
      (node (ref "H6") (pin "7") (pinfunction "7_7") (pintype "input"))
      (node (ref "H6") (pin "8") (pinfunction "8_8") (pintype "input"))
      (node (ref "U10") (pin "2") (pinfunction "DO(IO1)_2") (pintype "input"))
      (node (ref "U9") (pin "17") (pinfunction "17_17") (pintype "input"))
    )
    (net (code "61") (name "TIM1_CH1N{slash}TIM1_CH3{slash}PC3") (class "Default")
      (node (ref "C12") (pin "2") (pinfunction "2_2") (pintype "input"))
      (node (ref "H6") (pin "15") (pinfunction "15_15") (pintype "input"))
      (node (ref "H6") (pin "16") (pinfunction "16_16") (pintype "input"))
      (node (ref "R28") (pin "1") (pinfunction "1_1") (pintype "input"))
      (node (ref "U9") (pin "13") (pinfunction "13_13") (pintype "input"))
      (node (ref "USER_KEY") (pin "1") (pinfunction "A_1") (pintype "input"))
      (node (ref "USER_KEY") (pin "2") (pinfunction "B_2") (pintype "input"))
    )
    (net (code "62") (name "TODEMO_NRST") (class "Default")
      (node (ref "R11") (pin "2") (pinfunction "2_2") (pintype "input"))
      (node (ref "U3") (pin "18") (pinfunction "PB0ADC12_IN8TIM3_CH3_18") (pintype "input"))
      (node (ref "U8") (pin "3") (pinfunction "A_3") (pintype "input"))
    )
    (net (code "63") (name "TODEMO_SWCLK") (class "Default")
      (node (ref "U3") (pin "26") (pinfunction "PB13SPI2_SCKUSART3_CTSTIM1_CH1N_26") (pintype "input"))
      (node (ref "U7") (pin "3") (pinfunction "A_3") (pintype "input"))
    )
    (net (code "64") (name "TODEMO_SWDIO") (class "Default")
      (node (ref "R12") (pin "2") (pinfunction "2_2") (pintype "input"))
      (node (ref "R18") (pin "1") (pinfunction "1_1") (pintype "input"))
      (node (ref "U3") (pin "27") (pinfunction "PB14SPI2_MISOUSART3_RTSTIM1_CH2N_27") (pintype "input"))
      (node (ref "U6") (pin "3") (pinfunction "A_3") (pintype "input"))
    )
    (net (code "65") (name "TODEMO_UART_RX") (class "Default")
      (node (ref "R14") (pin "1") (pinfunction "1_1") (pintype "input"))
      (node (ref "U3") (pin "13") (pinfunction "PA3USART2_RXADC12_IN3TIM2_CH4_13") (pintype "input"))
      (node (ref "U5") (pin "3") (pinfunction "A_3") (pintype "input"))
    )
    (net (code "66") (name "TODEMO_UART_TX") (class "Default")
      (node (ref "U3") (pin "12") (pinfunction "PA2USART2_TXADC12_IN2TIM2_CH3_12") (pintype "input"))
      (node (ref "U4") (pin "3") (pinfunction "A_3") (pintype "input"))
    )
    (net (code "67") (name "USB_ENUM") (class "Default")
      (node (ref "R1") (pin "2") (pinfunction "2_2") (pintype "input"))
      (node (ref "U3") (pin "28") (pinfunction "PB15SPI2_MOSITIM1_CH3N_28") (pintype "input"))
    )
    (net (code "68") (name "unconnected-(U1-IO-Pad3)") (class "Default")
      (node (ref "U1") (pin "3") (pinfunction "IO_3") (pintype "input"))
    )
    (net (code "69") (name "unconnected-(U1-IO-Pad4)") (class "Default")
      (node (ref "U1") (pin "4") (pinfunction "IO_4") (pintype "input"))
    )
    (net (code "70") (name "unconnected-(U3-PA0_WKUPUSART2_CTSADC12_IN0TIM2_CH1_ETR-Pad10)") (class "Default")
      (node (ref "U3") (pin "10") (pinfunction "PA0_WKUPUSART2_CTSADC12_IN0TIM2_CH1_ETR_10") (pintype "input"))
    )
    (net (code "71") (name "unconnected-(U3-PA1USART2_RTSADC12_IN1TIM2_CH2-Pad11)") (class "Default")
      (node (ref "U3") (pin "11") (pinfunction "PA1USART2_RTSADC12_IN1TIM2_CH2_11") (pintype "input"))
    )
    (net (code "72") (name "unconnected-(U3-PA4SPI1_NSSUSART2_CKADC12_IN4-Pad14)") (class "Default")
      (node (ref "U3") (pin "14") (pinfunction "PA4SPI1_NSSUSART2_CKADC12_IN4_14") (pintype "input"))
    )
    (net (code "73") (name "unconnected-(U3-PA5SPI1_SCKADC12_IN5-Pad15)") (class "Default")
      (node (ref "U3") (pin "15") (pinfunction "PA5SPI1_SCKADC12_IN5_15") (pintype "input"))
    )
    (net (code "74") (name "unconnected-(U3-PA6SPI1_MISOADC12_IN6TIM3_CH1-Pad16)") (class "Default")
      (node (ref "U3") (pin "16") (pinfunction "PA6SPI1_MISOADC12_IN6TIM3_CH1_16") (pintype "input"))
    )
    (net (code "75") (name "unconnected-(U3-PA7SPI1_MOSIADC12_IN7TIM3_CH2-Pad17)") (class "Default")
      (node (ref "U3") (pin "17") (pinfunction "PA7SPI1_MOSIADC12_IN7TIM3_CH2_17") (pintype "input"))
    )
    (net (code "76") (name "unconnected-(U3-PA8USART1_CKTIM1_CH1MCO-Pad29)") (class "Default")
      (node (ref "U3") (pin "29") (pinfunction "PA8USART1_CKTIM1_CH1MCO_29") (pintype "input"))
    )
    (net (code "77") (name "unconnected-(U3-PA9USART1_TXTIM1_CH2-Pad30)") (class "Default")
      (node (ref "U3") (pin "30") (pinfunction "PA9USART1_TXTIM1_CH2_30") (pintype "input"))
    )
    (net (code "78") (name "unconnected-(U3-PA10USART1_RXTIM1_CH3-Pad31)") (class "Default")
      (node (ref "U3") (pin "31") (pinfunction "PA10USART1_RXTIM1_CH3_31") (pintype "input"))
    )
    (net (code "79") (name "unconnected-(U3-PA15JTDI-Pad38)") (class "Default")
      (node (ref "U3") (pin "38") (pinfunction "PA15JTDI_38") (pintype "input"))
    )
    (net (code "80") (name "unconnected-(U3-PB1ADC12_IN9TIM3_CH4-Pad19)") (class "Default")
      (node (ref "U3") (pin "19") (pinfunction "PB1ADC12_IN9TIM3_CH4_19") (pintype "input"))
    )
    (net (code "81") (name "unconnected-(U3-PB2BOOT1-Pad20)") (class "Default")
      (node (ref "U3") (pin "20") (pinfunction "PB2BOOT1_20") (pintype "input"))
    )
    (net (code "82") (name "unconnected-(U3-PB3JTDO-Pad39)") (class "Default")
      (node (ref "U3") (pin "39") (pinfunction "PB3JTDO_39") (pintype "input"))
    )
    (net (code "83") (name "unconnected-(U3-PB4NJTRST-Pad40)") (class "Default")
      (node (ref "U3") (pin "40") (pinfunction "PB4NJTRST_40") (pintype "input"))
    )
    (net (code "84") (name "unconnected-(U3-PB5I2C1_SMBA-Pad41)") (class "Default")
      (node (ref "U3") (pin "41") (pinfunction "PB5I2C1_SMBA_41") (pintype "input"))
    )
    (net (code "85") (name "unconnected-(U3-PB6I2C1_SCLTIM4_CH1-Pad42)") (class "Default")
      (node (ref "U3") (pin "42") (pinfunction "PB6I2C1_SCLTIM4_CH1_42") (pintype "input"))
    )
    (net (code "86") (name "unconnected-(U3-PB8TIM4_CH3-Pad45)") (class "Default")
      (node (ref "U3") (pin "45") (pinfunction "PB8TIM4_CH3_45") (pintype "input"))
    )
    (net (code "87") (name "unconnected-(U3-PB9TIM4_CH4-Pad46)") (class "Default")
      (node (ref "U3") (pin "46") (pinfunction "PB9TIM4_CH4_46") (pintype "input"))
    )
    (net (code "88") (name "unconnected-(U3-PB10I2C2_SCLUSART3_TX-Pad21)") (class "Default")
      (node (ref "U3") (pin "21") (pinfunction "PB10I2C2_SCLUSART3_TX_21") (pintype "input"))
    )
    (net (code "89") (name "unconnected-(U3-PB11I2C2_SDAUSART3_RX--Pad22)") (class "Default")
      (node (ref "U3") (pin "22") (pinfunction "PB11I2C2_SDAUSART3_RX-_22") (pintype "input"))
    )
    (net (code "90") (name "unconnected-(U3-VBAT-Pad1)") (class "Default")
      (node (ref "U3") (pin "1") (pinfunction "VBAT_1") (pintype "input"))
    )
    (net (code "91") (name "unconnected-(USB1-SBU1-PadA8)") (class "Default")
      (node (ref "USB1") (pin "A8") (pinfunction "SBU1_A8") (pintype "input"))
    )
    (net (code "92") (name "unconnected-(USB1-SBU2-PadB8)") (class "Default")
      (node (ref "USB1") (pin "B8") (pinfunction "SBU2_B8") (pintype "input"))
    )
  )
)
